# LcsNodes-Extension-Turnout-Servo-and-Rel.net
KiCad netlist of a schematic drawn in EasyEDA
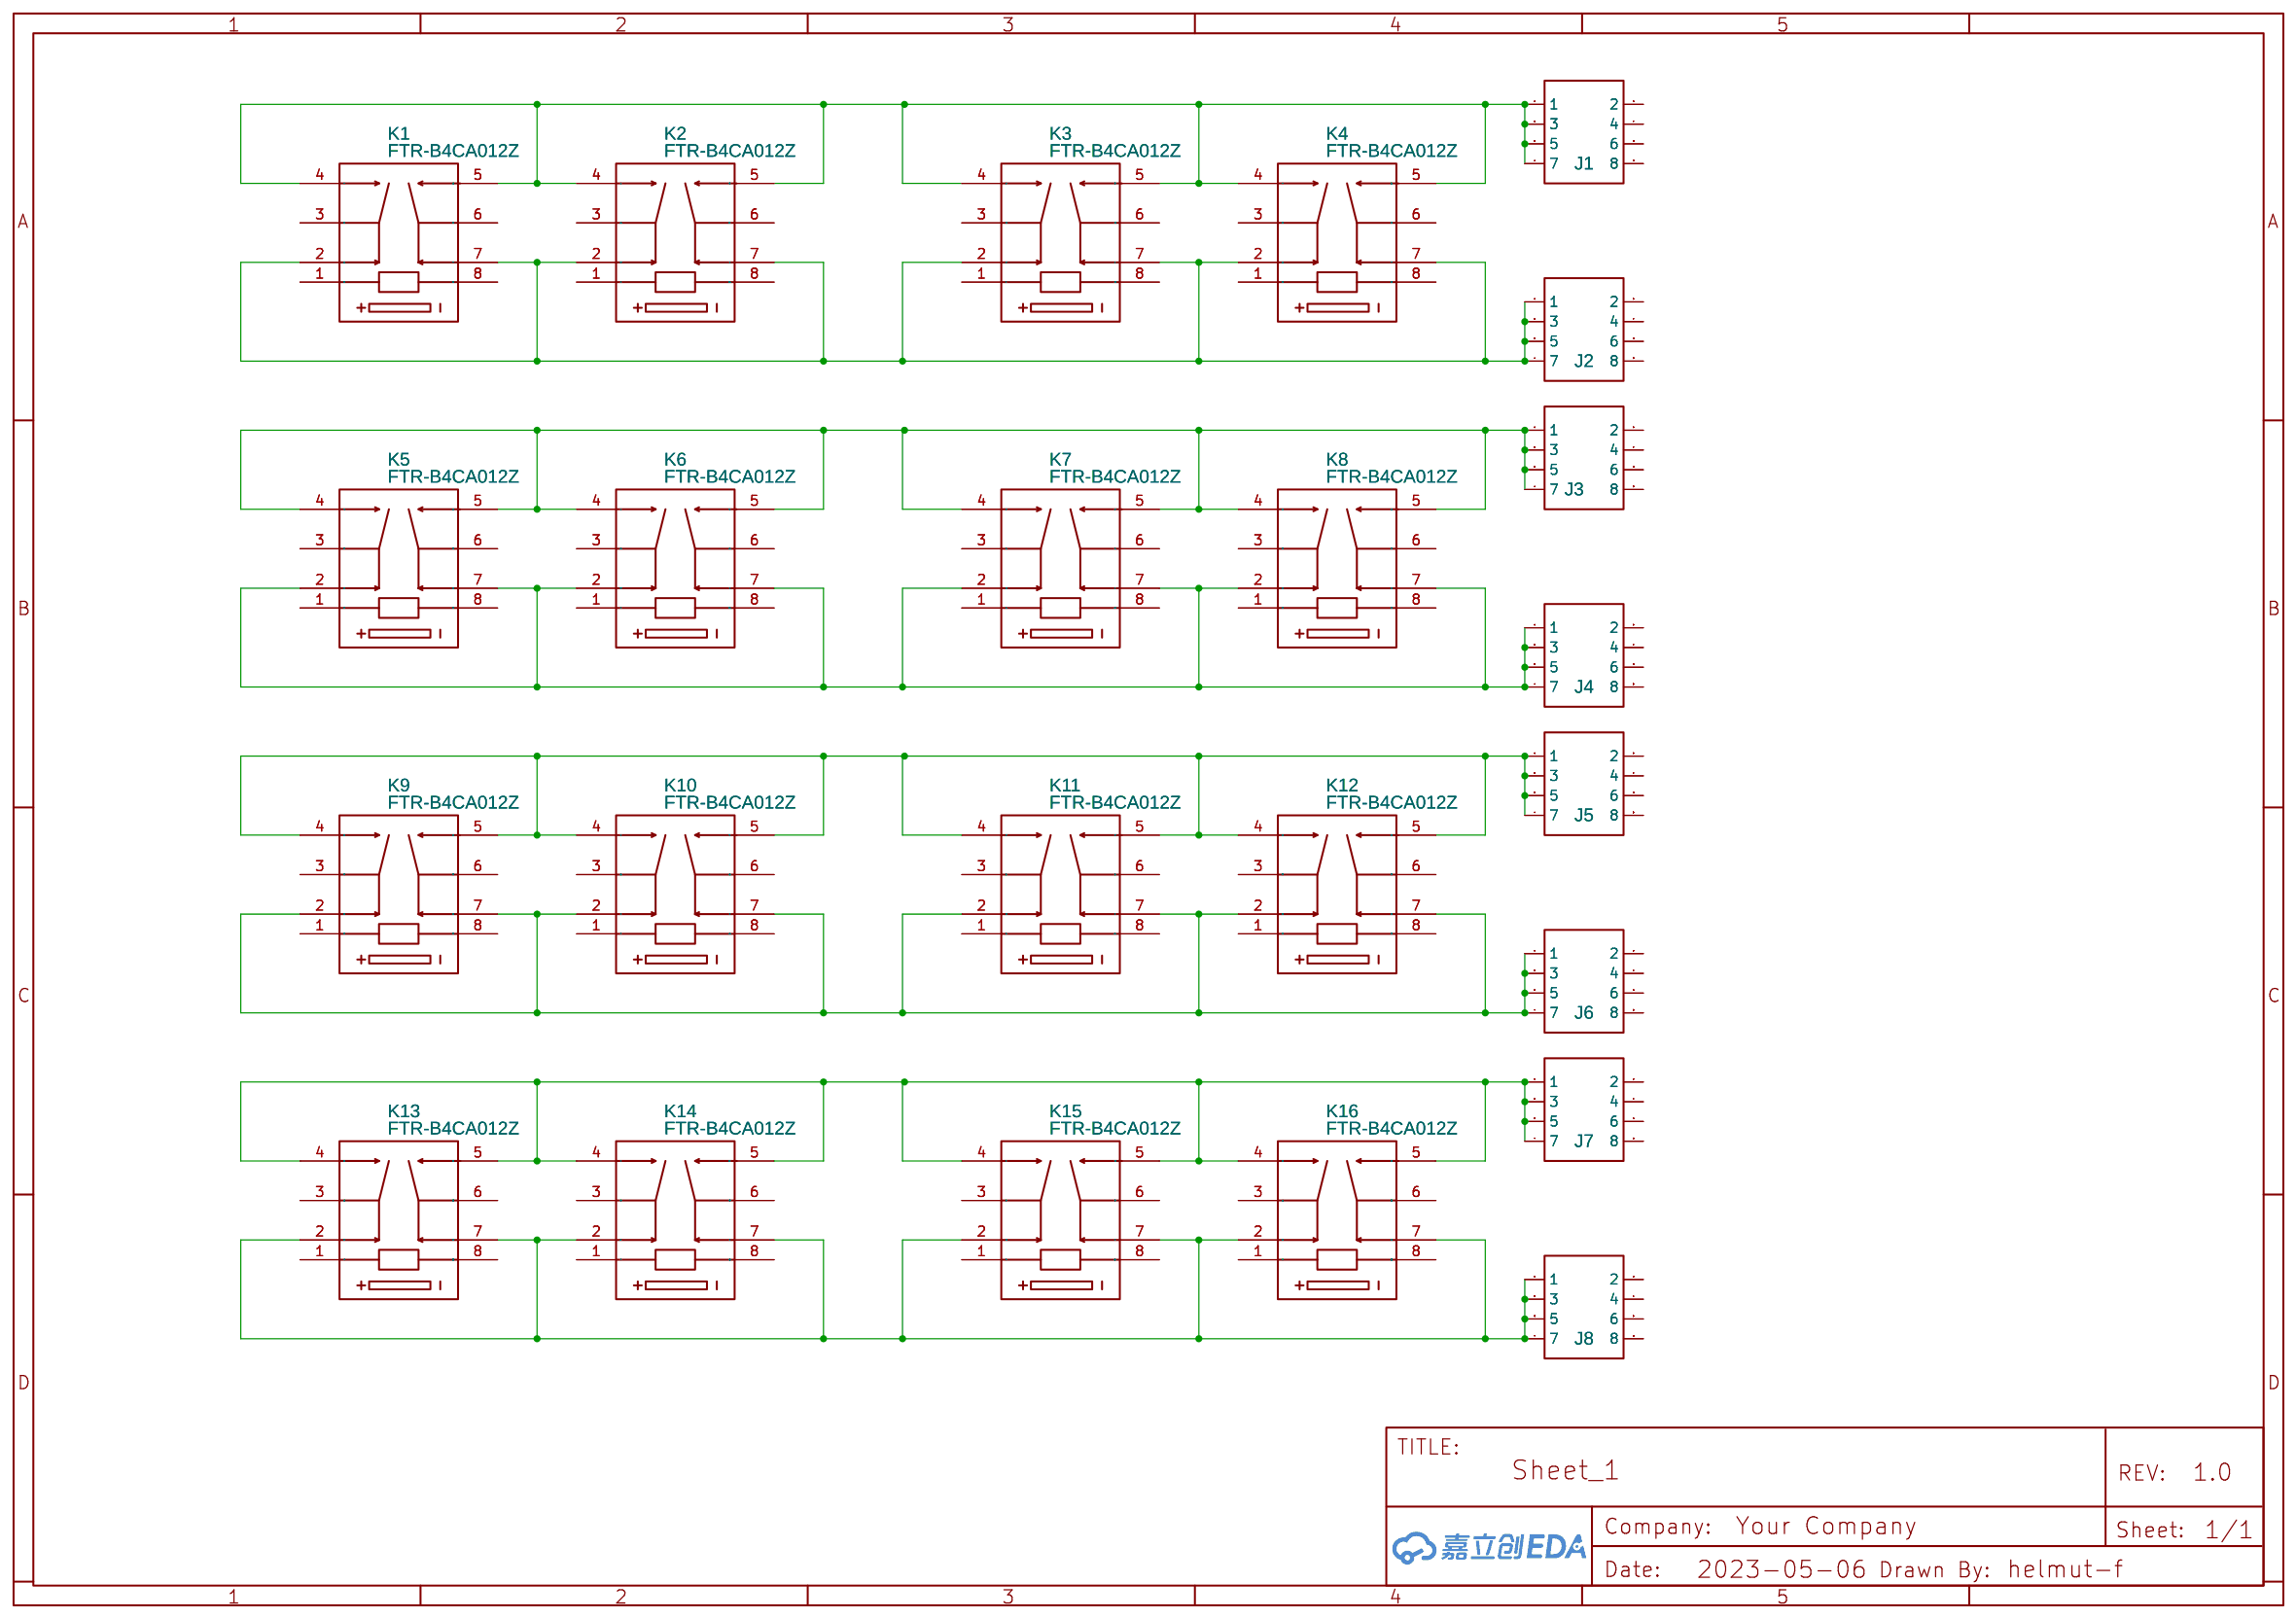
[diagram p0: Sheet_1]
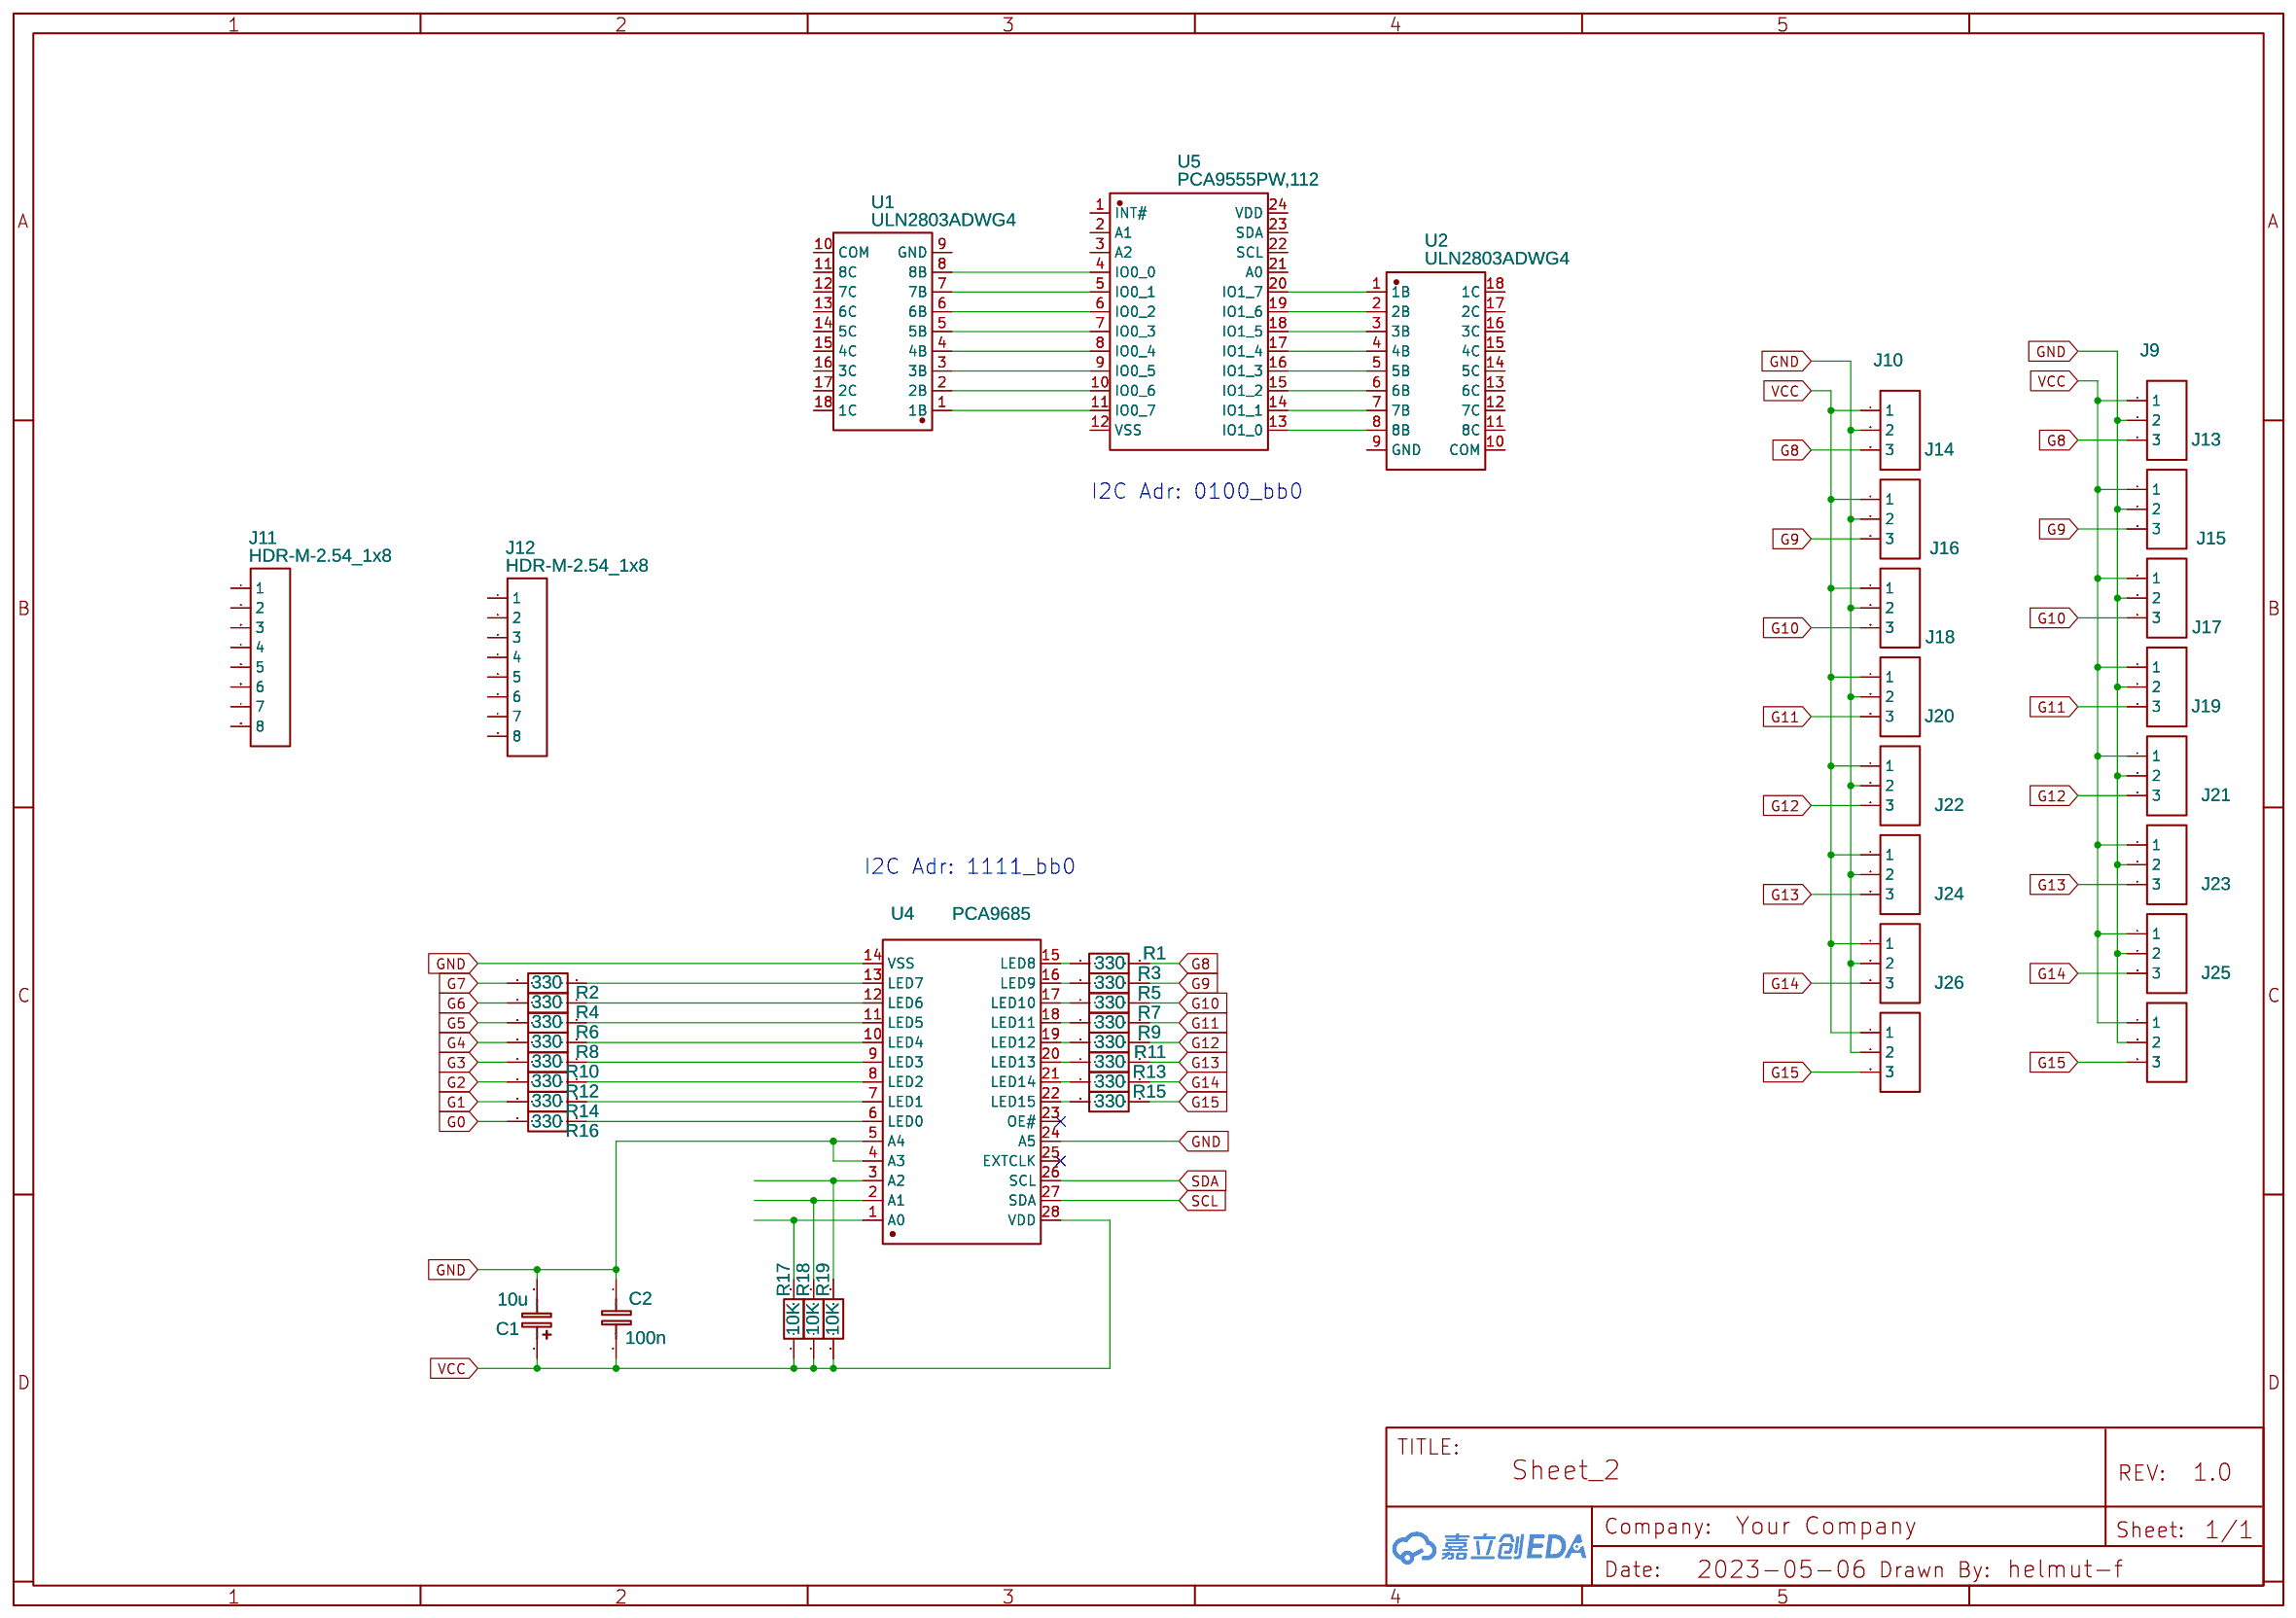
[diagram p1: Sheet_2]
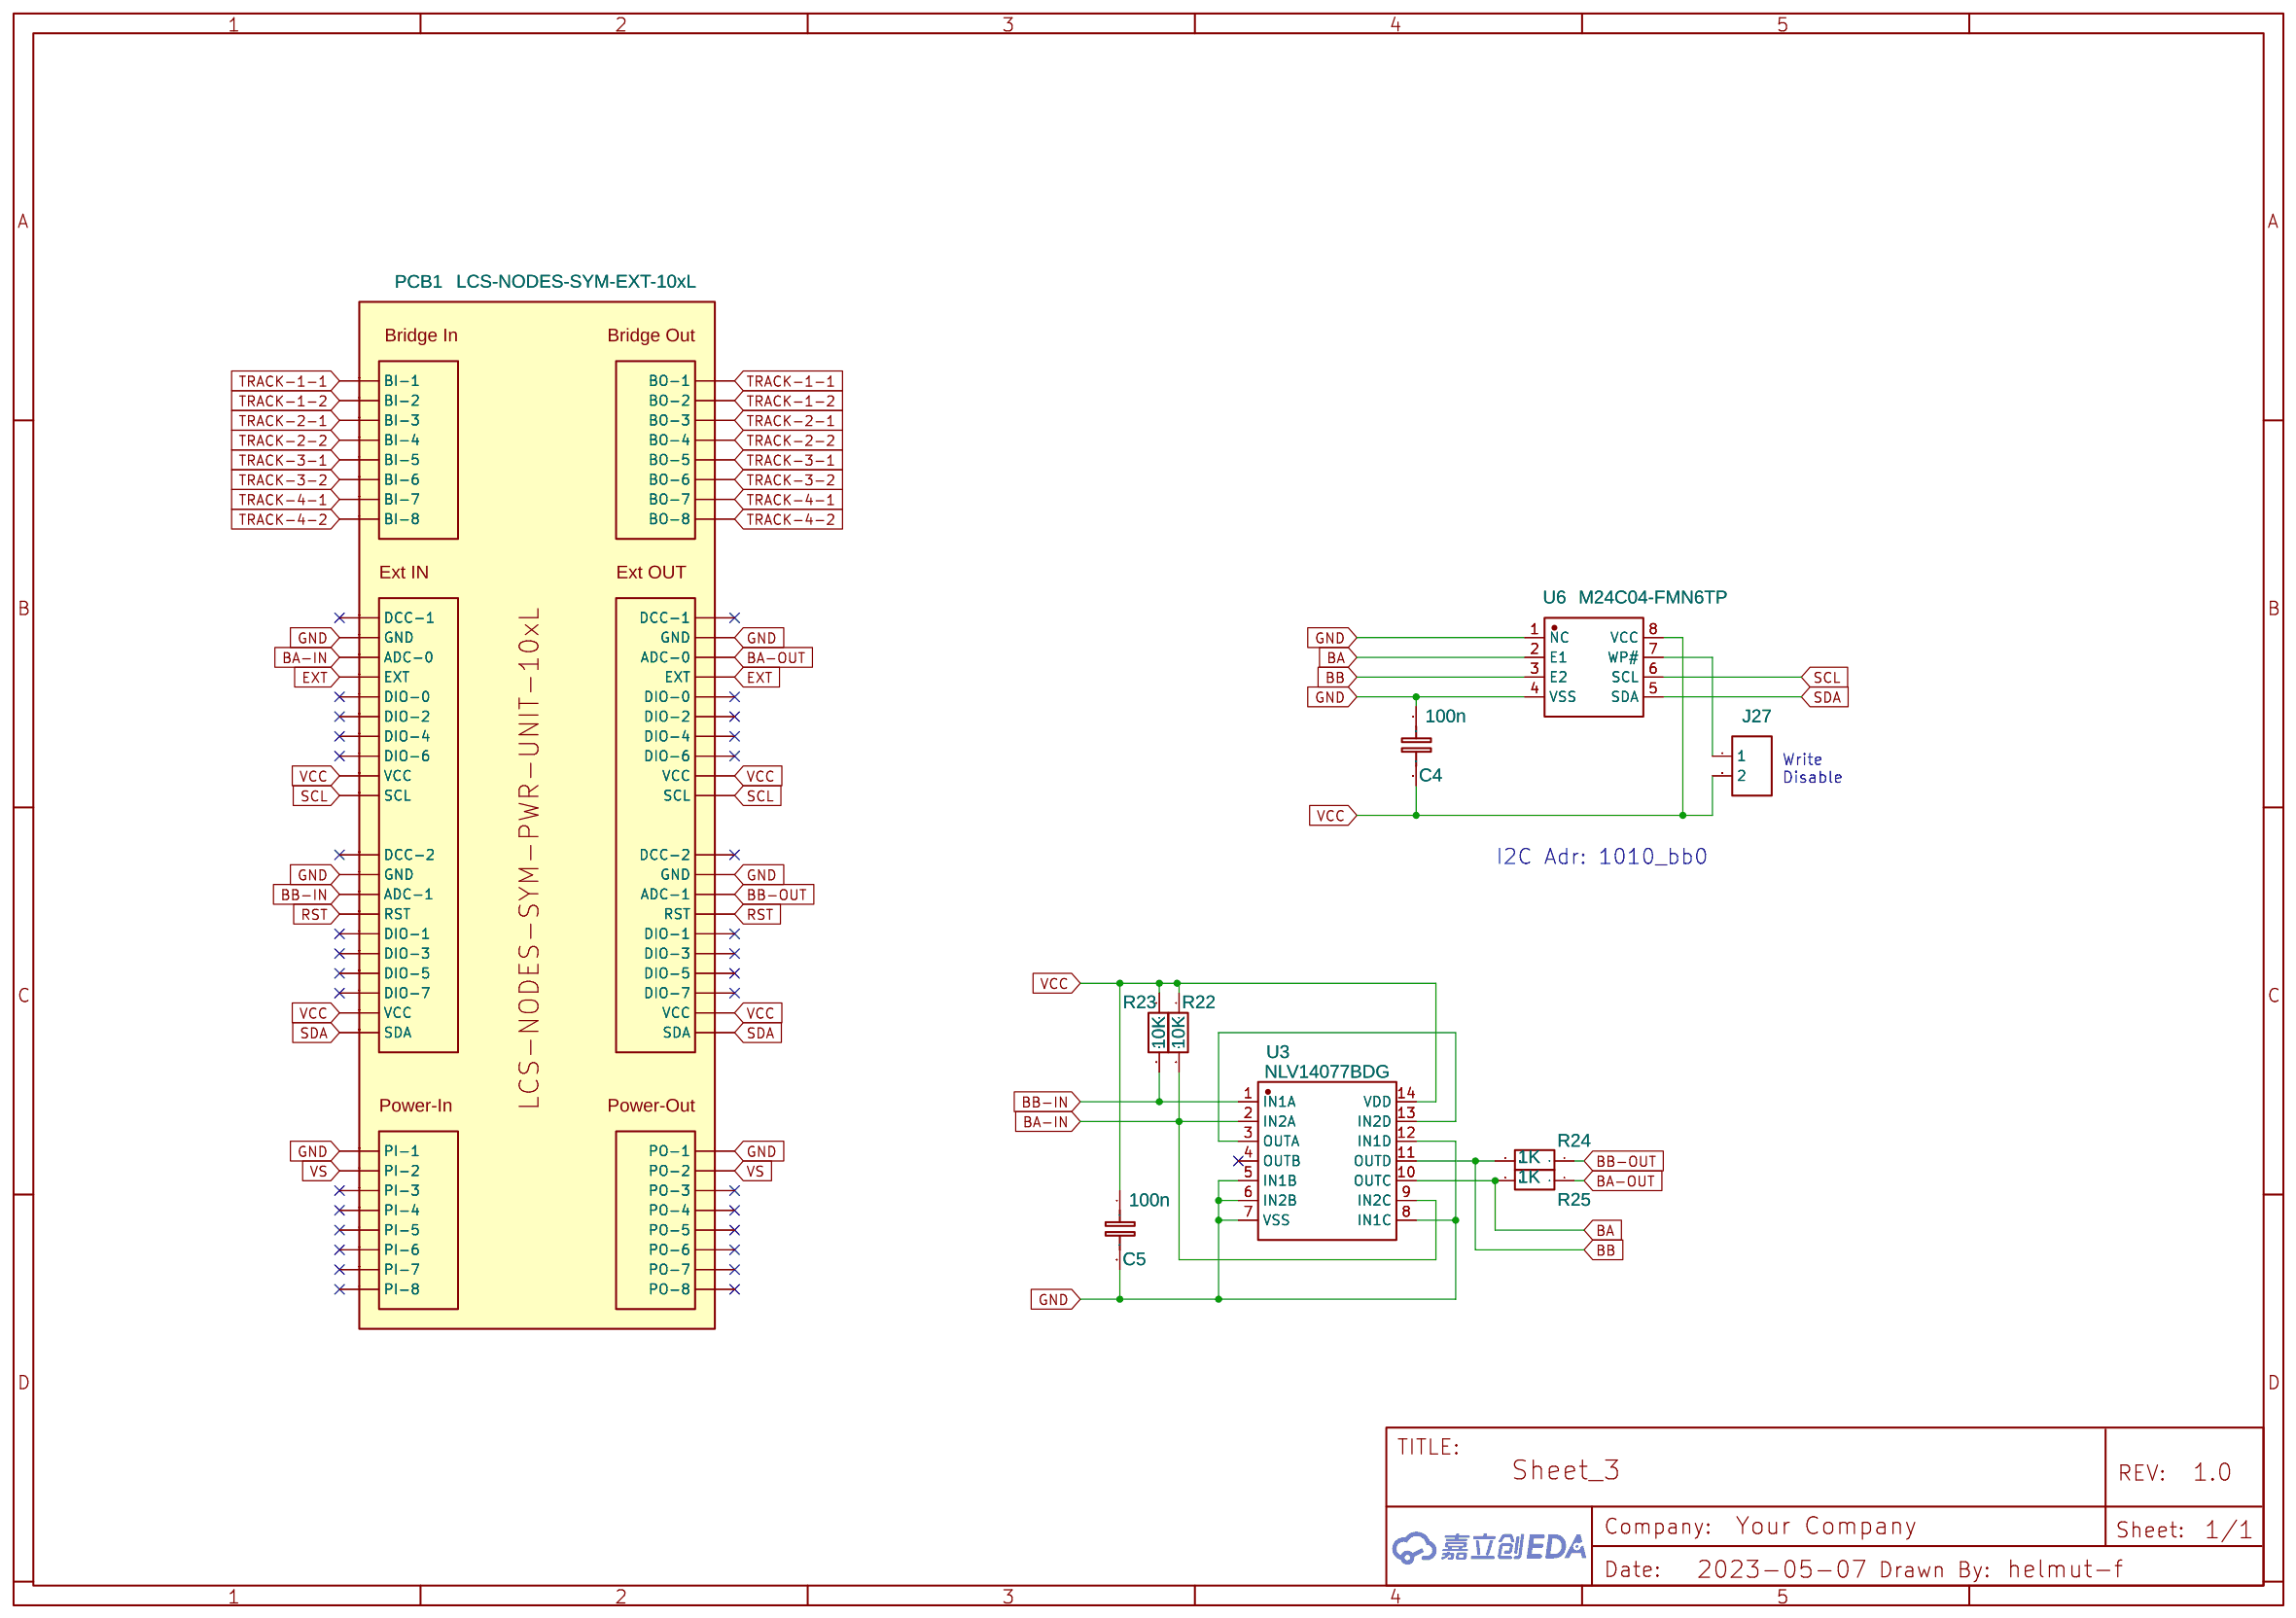
[diagram p2: Sheet_3]

(export (version "E")
  (design (tool "Eeschema 10.0.6"))
  (components
    (comp (ref "J1")
      (value "HDR-M-2.54_2x4")
      (fields (field (name "BOM_Supplier Part") "C58363"))
      (libsource (lib "") (part "HDR-M-2.54_2x4"))
    )
    (comp (ref "J2")
      (value "HDR-M-2.54_2x4")
      (fields (field (name "BOM_Supplier Part") "C58363"))
      (libsource (lib "") (part "HDR-M-2.54_2x4"))
    )
    (comp (ref "J3")
      (value "HDR-M-2.54_2x4")
      (fields (field (name "BOM_Supplier Part") "C58363"))
      (libsource (lib "") (part "HDR-M-2.54_2x4"))
    )
    (comp (ref "J4")
      (value "HDR-M-2.54_2x4")
      (fields (field (name "BOM_Supplier Part") "C58363"))
      (libsource (lib "") (part "HDR-M-2.54_2x4"))
    )
    (comp (ref "J5")
      (value "HDR-M-2.54_2x4")
      (fields (field (name "BOM_Supplier Part") "C58363"))
      (libsource (lib "") (part "HDR-M-2.54_2x4"))
    )
    (comp (ref "J6")
      (value "HDR-M-2.54_2x4")
      (fields (field (name "BOM_Supplier Part") "C58363"))
      (libsource (lib "") (part "HDR-M-2.54_2x4"))
    )
    (comp (ref "J7")
      (value "HDR-M-2.54_2x4")
      (fields (field (name "BOM_Supplier Part") "C58363"))
      (libsource (lib "") (part "HDR-M-2.54_2x4"))
    )
    (comp (ref "J8")
      (value "HDR-M-2.54_2x4")
      (fields (field (name "BOM_Supplier Part") "C58363"))
      (libsource (lib "") (part "HDR-M-2.54_2x4"))
    )
    (comp (ref "K1")
      (value "FTR-B4CA012Z")
      (fields (field (name "BOM_Supplier Part") "C1222347"))
      (libsource (lib "") (part "FTR-B4CA012Z"))
    )
    (comp (ref "K2")
      (value "FTR-B4CA012Z")
      (fields (field (name "BOM_Supplier Part") "C1222347"))
      (libsource (lib "") (part "FTR-B4CA012Z"))
    )
    (comp (ref "K3")
      (value "FTR-B4CA012Z")
      (fields (field (name "BOM_Supplier Part") "C1222347"))
      (libsource (lib "") (part "FTR-B4CA012Z"))
    )
    (comp (ref "K4")
      (value "FTR-B4CA012Z")
      (fields (field (name "BOM_Supplier Part") "C1222347"))
      (libsource (lib "") (part "FTR-B4CA012Z"))
    )
    (comp (ref "K5")
      (value "FTR-B4CA012Z")
      (fields (field (name "BOM_Supplier Part") "C1222347"))
      (libsource (lib "") (part "FTR-B4CA012Z"))
    )
    (comp (ref "K6")
      (value "FTR-B4CA012Z")
      (fields (field (name "BOM_Supplier Part") "C1222347"))
      (libsource (lib "") (part "FTR-B4CA012Z"))
    )
    (comp (ref "K7")
      (value "FTR-B4CA012Z")
      (fields (field (name "BOM_Supplier Part") "C1222347"))
      (libsource (lib "") (part "FTR-B4CA012Z"))
    )
    (comp (ref "K8")
      (value "FTR-B4CA012Z")
      (fields (field (name "BOM_Supplier Part") "C1222347"))
      (libsource (lib "") (part "FTR-B4CA012Z"))
    )
    (comp (ref "K9")
      (value "FTR-B4CA012Z")
      (fields (field (name "BOM_Supplier Part") "C1222347"))
      (libsource (lib "") (part "FTR-B4CA012Z"))
    )
    (comp (ref "K10")
      (value "FTR-B4CA012Z")
      (fields (field (name "BOM_Supplier Part") "C1222347"))
      (libsource (lib "") (part "FTR-B4CA012Z"))
    )
    (comp (ref "K11")
      (value "FTR-B4CA012Z")
      (fields (field (name "BOM_Supplier Part") "C1222347"))
      (libsource (lib "") (part "FTR-B4CA012Z"))
    )
    (comp (ref "K12")
      (value "FTR-B4CA012Z")
      (fields (field (name "BOM_Supplier Part") "C1222347"))
      (libsource (lib "") (part "FTR-B4CA012Z"))
    )
    (comp (ref "K13")
      (value "FTR-B4CA012Z")
      (fields (field (name "BOM_Supplier Part") "C1222347"))
      (libsource (lib "") (part "FTR-B4CA012Z"))
    )
    (comp (ref "K14")
      (value "FTR-B4CA012Z")
      (fields (field (name "BOM_Supplier Part") "C1222347"))
      (libsource (lib "") (part "FTR-B4CA012Z"))
    )
    (comp (ref "K15")
      (value "FTR-B4CA012Z")
      (fields (field (name "BOM_Supplier Part") "C1222347"))
      (libsource (lib "") (part "FTR-B4CA012Z"))
    )
    (comp (ref "K16")
      (value "FTR-B4CA012Z")
      (fields (field (name "BOM_Supplier Part") "C1222347"))
      (libsource (lib "") (part "FTR-B4CA012Z"))
    )
    (comp (ref "C1") (value "10u") (libsource (lib "") (part "CE_TH_D4.0×F1.5_EU")))
    (comp (ref "C2") (value "100n") (libsource (lib "") (part "C_0603_EU")))
    (comp (ref "J9")
      (value "HDR-M-2.54_1x3")
      (fields (field (name "BOM_Supplier Part") "C180248"))
      (libsource (lib "") (part "HDR-M-2.54_1x3"))
    )
    (comp (ref "J10")
      (value "HDR-M-2.54_1x3")
      (fields (field (name "BOM_Supplier Part") "C180248"))
      (libsource (lib "") (part "HDR-M-2.54_1x3"))
    )
    (comp (ref "J11")
      (value "HDR-M-2.54_1x8")
      (fields (field (name "BOM_Supplier Part") "C190820"))
      (libsource (lib "") (part "HDR-M-2.54_1x8"))
    )
    (comp (ref "J12")
      (value "HDR-M-2.54_1x8")
      (fields (field (name "BOM_Supplier Part") "C190820"))
      (libsource (lib "") (part "HDR-M-2.54_1x8"))
    )
    (comp (ref "J13")
      (value "HDR-M-2.54_1x3")
      (fields (field (name "BOM_Supplier Part") "C180248"))
      (libsource (lib "") (part "HDR-M-2.54_1x3"))
    )
    (comp (ref "J14")
      (value "HDR-M-2.54_1x3")
      (fields (field (name "BOM_Supplier Part") "C180248"))
      (libsource (lib "") (part "HDR-M-2.54_1x3"))
    )
    (comp (ref "J15")
      (value "HDR-M-2.54_1x3")
      (fields (field (name "BOM_Supplier Part") "C180248"))
      (libsource (lib "") (part "HDR-M-2.54_1x3"))
    )
    (comp (ref "J16")
      (value "HDR-M-2.54_1x3")
      (fields (field (name "BOM_Supplier Part") "C180248"))
      (libsource (lib "") (part "HDR-M-2.54_1x3"))
    )
    (comp (ref "J17")
      (value "HDR-M-2.54_1x3")
      (fields (field (name "BOM_Supplier Part") "C180248"))
      (libsource (lib "") (part "HDR-M-2.54_1x3"))
    )
    (comp (ref "J18")
      (value "HDR-M-2.54_1x3")
      (fields (field (name "BOM_Supplier Part") "C180248"))
      (libsource (lib "") (part "HDR-M-2.54_1x3"))
    )
    (comp (ref "J19")
      (value "HDR-M-2.54_1x3")
      (fields (field (name "BOM_Supplier Part") "C180248"))
      (libsource (lib "") (part "HDR-M-2.54_1x3"))
    )
    (comp (ref "J20")
      (value "HDR-M-2.54_1x3")
      (fields (field (name "BOM_Supplier Part") "C180248"))
      (libsource (lib "") (part "HDR-M-2.54_1x3"))
    )
    (comp (ref "J21")
      (value "HDR-M-2.54_1x3")
      (fields (field (name "BOM_Supplier Part") "C180248"))
      (libsource (lib "") (part "HDR-M-2.54_1x3"))
    )
    (comp (ref "J22")
      (value "HDR-M-2.54_1x3")
      (fields (field (name "BOM_Supplier Part") "C180248"))
      (libsource (lib "") (part "HDR-M-2.54_1x3"))
    )
    (comp (ref "J23")
      (value "HDR-M-2.54_1x3")
      (fields (field (name "BOM_Supplier Part") "C180248"))
      (libsource (lib "") (part "HDR-M-2.54_1x3"))
    )
    (comp (ref "J24")
      (value "HDR-M-2.54_1x3")
      (fields (field (name "BOM_Supplier Part") "C180248"))
      (libsource (lib "") (part "HDR-M-2.54_1x3"))
    )
    (comp (ref "J25")
      (value "HDR-M-2.54_1x3")
      (fields (field (name "BOM_Supplier Part") "C180248"))
      (libsource (lib "") (part "HDR-M-2.54_1x3"))
    )
    (comp (ref "J26")
      (value "HDR-M-2.54_1x3")
      (fields (field (name "BOM_Supplier Part") "C180248"))
      (libsource (lib "") (part "HDR-M-2.54_1x3"))
    )
    (comp (ref "R1") (value "330") (libsource (lib "") (part "R_AXIAL-0.3_EU")))
    (comp (ref "R2") (value "330") (libsource (lib "") (part "R_AXIAL-0.3_EU_1")))
    (comp (ref "R3") (value "330") (libsource (lib "") (part "R_AXIAL-0.3_EU")))
    (comp (ref "R4") (value "330") (libsource (lib "") (part "R_AXIAL-0.3_EU_1")))
    (comp (ref "R5") (value "330") (libsource (lib "") (part "R_AXIAL-0.3_EU")))
    (comp (ref "R6") (value "330") (libsource (lib "") (part "R_AXIAL-0.3_EU_1")))
    (comp (ref "R7") (value "330") (libsource (lib "") (part "R_AXIAL-0.3_EU")))
    (comp (ref "R8") (value "330") (libsource (lib "") (part "R_AXIAL-0.3_EU_1")))
    (comp (ref "R9") (value "330") (libsource (lib "") (part "R_AXIAL-0.3_EU")))
    (comp (ref "R10") (value "330") (libsource (lib "") (part "R_AXIAL-0.3_EU_1")))
    (comp (ref "R11") (value "330") (libsource (lib "") (part "R_AXIAL-0.3_EU")))
    (comp (ref "R12") (value "330") (libsource (lib "") (part "R_AXIAL-0.3_EU_1")))
    (comp (ref "R13") (value "330") (libsource (lib "") (part "R_AXIAL-0.3_EU")))
    (comp (ref "R14") (value "330") (libsource (lib "") (part "R_AXIAL-0.3_EU_1")))
    (comp (ref "R15") (value "330") (libsource (lib "") (part "R_AXIAL-0.3_EU")))
    (comp (ref "R16") (value "330") (libsource (lib "") (part "R_AXIAL-0.3_EU_1")))
    (comp (ref "R17") (value "10K") (libsource (lib "") (part "R_1206_EU")))
    (comp (ref "R18") (value "10K") (libsource (lib "") (part "R_1206_EU")))
    (comp (ref "R19") (value "10K") (libsource (lib "") (part "R_1206_EU")))
    (comp (ref "U1")
      (value "ULN2803ADWG4")
      (fields (field (name "BOM_Supplier Part") "C4365973"))
      (libsource (lib "") (part "ULN2803ADWG4"))
    )
    (comp (ref "U2")
      (value "ULN2803ADWG4")
      (fields (field (name "BOM_Supplier Part") "C4365973"))
      (libsource (lib "") (part "ULN2803ADWG4_1"))
    )
    (comp (ref "U4")
      (value "PCA9685")
      (fields
        (field (name "BOM_Manufacturer Part") "PCA9685PW/Q900,118")
        (field (name "BOM_Supplier Part") "C92206")
      )
      (libsource (lib "") (part "PCA9685PW/Q900,118"))
    )
    (comp (ref "U5")
      (value "PCA9555PW,112")
      (fields (field (name "BOM_Supplier Part") "C2688893"))
      (libsource (lib "") (part "PCA9555PW,112"))
    )
    (comp (ref "C4") (value "100n") (libsource (lib "") (part "C_0603_EU")))
    (comp (ref "C5") (value "100n") (libsource (lib "") (part "C_0603_EU")))
    (comp (ref "J27") (value "HDR-M-2.54_1x2") (libsource (lib "") (part "HDR-M-2.54_1x2")))
    (comp (ref "PCB1") (value "LCS-NODES-SYM-EXT-10xL") (libsource (lib "") (part "LCS-NODES-SYM-EXT-10xL")))
    (comp (ref "R22") (value "10K") (libsource (lib "") (part "R_AXIAL-0.3_EU_1")))
    (comp (ref "R23") (value "10K") (libsource (lib "") (part "R_AXIAL-0.3_EU_1")))
    (comp (ref "R24") (value "1K") (libsource (lib "") (part "R_AXIAL-0.3_EU")))
    (comp (ref "R25") (value "1K") (libsource (lib "") (part "R_AXIAL-0.3_EU")))
    (comp (ref "U3")
      (value "NLV14077BDG")
      (fields (field (name "Manufacturer") "onsemi(安森美)"))
      (libsource (lib "") (part "NLV14077BDG"))
    )
    (comp (ref "U6")
      (value "M24C04-FMN6TP")
      (fields (field (name "Manufacturer") "ST(意法半导体)"))
      (libsource (lib "") (part "M24C04-FMN6TP"))
    )
  )
  (nets
    (net (code "1") (name "BA") (class "Default")
      (node (ref "R25") (pin "2") (pinfunction "2_2") (pintype "unspecified"))
      (node (ref "U3") (pin "10") (pinfunction "OUTC_10") (pintype "unspecified"))
      (node (ref "U6") (pin "2") (pinfunction "E1_2") (pintype "unspecified"))
    )
    (net (code "2") (name "BA-IN") (class "Default")
      (node (ref "PCB1") (pin "22") (pinfunction "ADC-0_22") (pintype "unspecified"))
      (node (ref "R22") (pin "2") (pinfunction "2_2") (pintype "unspecified"))
      (node (ref "U3") (pin "2") (pinfunction "IN2A_2") (pintype "unspecified"))
      (node (ref "U3") (pin "9") (pinfunction "IN2C_9") (pintype "unspecified"))
    )
    (net (code "3") (name "BA-OUT") (class "Default")
      (node (ref "PCB1") (pin "62") (pinfunction "ADC-0_62") (pintype "unspecified"))
      (node (ref "R25") (pin "1") (pinfunction "1_1") (pintype "unspecified"))
    )
    (net (code "4") (name "BB") (class "Default")
      (node (ref "R24") (pin "2") (pinfunction "2_2") (pintype "unspecified"))
      (node (ref "U3") (pin "11") (pinfunction "OUTD_11") (pintype "unspecified"))
      (node (ref "U6") (pin "3") (pinfunction "E2_3") (pintype "unspecified"))
    )
    (net (code "5") (name "BB-IN") (class "Default")
      (node (ref "PCB1") (pin "32") (pinfunction "ADC-1_32") (pintype "unspecified"))
      (node (ref "R23") (pin "2") (pinfunction "2_2") (pintype "unspecified"))
      (node (ref "U3") (pin "1") (pinfunction "IN1A_1") (pintype "unspecified"))
    )
    (net (code "6") (name "BB-OUT") (class "Default")
      (node (ref "PCB1") (pin "72") (pinfunction "ADC-1_72") (pintype "unspecified"))
      (node (ref "R24") (pin "1") (pinfunction "1_1") (pintype "unspecified"))
    )
    (net (code "7") (name "EXT") (class "Default")
      (node (ref "PCB1") (pin "23") (pinfunction "EXT_23") (pintype "unspecified"))
      (node (ref "PCB1") (pin "63") (pinfunction "EXT_63") (pintype "unspecified"))
    )
    (net (code "8") (name "G0") (class "Default")
      (node (ref "R16") (pin "2") (pinfunction "2_2") (pintype "unspecified"))
    )
    (net (code "9") (name "G1") (class "Default")
      (node (ref "R14") (pin "2") (pinfunction "2_2") (pintype "unspecified"))
    )
    (net (code "10") (name "G2") (class "Default")
      (node (ref "R12") (pin "2") (pinfunction "2_2") (pintype "unspecified"))
    )
    (net (code "11") (name "G3") (class "Default")
      (node (ref "R10") (pin "2") (pinfunction "2_2") (pintype "unspecified"))
    )
    (net (code "12") (name "G4") (class "Default")
      (node (ref "R8") (pin "2") (pinfunction "2_2") (pintype "unspecified"))
    )
    (net (code "13") (name "G5") (class "Default")
      (node (ref "R6") (pin "2") (pinfunction "2_2") (pintype "unspecified"))
    )
    (net (code "14") (name "G6") (class "Default")
      (node (ref "R4") (pin "2") (pinfunction "2_2") (pintype "unspecified"))
    )
    (net (code "15") (name "G7") (class "Default")
      (node (ref "R2") (pin "2") (pinfunction "2_2") (pintype "unspecified"))
    )
    (net (code "16") (name "G8") (class "Default")
      (node (ref "J10") (pin "3") (pinfunction "3_3") (pintype "input"))
      (node (ref "J9") (pin "3") (pinfunction "3_3") (pintype "input"))
      (node (ref "R1") (pin "2") (pinfunction "2_2") (pintype "unspecified"))
    )
    (net (code "17") (name "G9") (class "Default")
      (node (ref "J13") (pin "3") (pinfunction "3_3") (pintype "input"))
      (node (ref "J14") (pin "3") (pinfunction "3_3") (pintype "input"))
      (node (ref "R3") (pin "2") (pinfunction "2_2") (pintype "unspecified"))
    )
    (net (code "18") (name "G10") (class "Default")
      (node (ref "J15") (pin "3") (pinfunction "3_3") (pintype "input"))
      (node (ref "J16") (pin "3") (pinfunction "3_3") (pintype "input"))
      (node (ref "R5") (pin "2") (pinfunction "2_2") (pintype "unspecified"))
    )
    (net (code "19") (name "G11") (class "Default")
      (node (ref "J17") (pin "3") (pinfunction "3_3") (pintype "input"))
      (node (ref "J18") (pin "3") (pinfunction "3_3") (pintype "input"))
      (node (ref "R7") (pin "2") (pinfunction "2_2") (pintype "unspecified"))
    )
    (net (code "20") (name "G12") (class "Default")
      (node (ref "J19") (pin "3") (pinfunction "3_3") (pintype "input"))
      (node (ref "J20") (pin "3") (pinfunction "3_3") (pintype "input"))
      (node (ref "R9") (pin "2") (pinfunction "2_2") (pintype "unspecified"))
    )
    (net (code "21") (name "G13") (class "Default")
      (node (ref "J21") (pin "3") (pinfunction "3_3") (pintype "input"))
      (node (ref "J22") (pin "3") (pinfunction "3_3") (pintype "input"))
      (node (ref "R11") (pin "2") (pinfunction "2_2") (pintype "unspecified"))
    )
    (net (code "22") (name "G14") (class "Default")
      (node (ref "J23") (pin "3") (pinfunction "3_3") (pintype "input"))
      (node (ref "J24") (pin "3") (pinfunction "3_3") (pintype "input"))
      (node (ref "R13") (pin "2") (pinfunction "2_2") (pintype "unspecified"))
    )
    (net (code "23") (name "G15") (class "Default")
      (node (ref "J25") (pin "3") (pinfunction "3_3") (pintype "input"))
      (node (ref "J26") (pin "3") (pinfunction "3_3") (pintype "input"))
      (node (ref "R15") (pin "2") (pinfunction "2_2") (pintype "unspecified"))
    )
    (net (code "24") (name "GND") (class "Default")
      (node (ref "C1") (pin "2") (pinfunction "2_2") (pintype "unspecified"))
      (node (ref "C2") (pin "1") (pinfunction "1_1") (pintype "unspecified"))
      (node (ref "C4") (pin "1") (pinfunction "1_1") (pintype "unspecified"))
      (node (ref "C5") (pin "2") (pinfunction "2_2") (pintype "unspecified"))
      (node (ref "J10") (pin "2") (pinfunction "2_2") (pintype "input"))
      (node (ref "J13") (pin "2") (pinfunction "2_2") (pintype "input"))
      (node (ref "J14") (pin "2") (pinfunction "2_2") (pintype "input"))
      (node (ref "J15") (pin "2") (pinfunction "2_2") (pintype "input"))
      (node (ref "J16") (pin "2") (pinfunction "2_2") (pintype "input"))
      (node (ref "J17") (pin "2") (pinfunction "2_2") (pintype "input"))
      (node (ref "J18") (pin "2") (pinfunction "2_2") (pintype "input"))
      (node (ref "J19") (pin "2") (pinfunction "2_2") (pintype "input"))
      (node (ref "J20") (pin "2") (pinfunction "2_2") (pintype "input"))
      (node (ref "J21") (pin "2") (pinfunction "2_2") (pintype "input"))
      (node (ref "J22") (pin "2") (pinfunction "2_2") (pintype "input"))
      (node (ref "J23") (pin "2") (pinfunction "2_2") (pintype "input"))
      (node (ref "J24") (pin "2") (pinfunction "2_2") (pintype "input"))
      (node (ref "J25") (pin "2") (pinfunction "2_2") (pintype "input"))
      (node (ref "J26") (pin "2") (pinfunction "2_2") (pintype "input"))
      (node (ref "J9") (pin "2") (pinfunction "2_2") (pintype "input"))
      (node (ref "PCB1") (pin "21") (pinfunction "GND_21") (pintype "unspecified"))
      (node (ref "PCB1") (pin "31") (pinfunction "GND_31") (pintype "unspecified"))
      (node (ref "PCB1") (pin "40") (pinfunction "PI-1_40") (pintype "unspecified"))
      (node (ref "PCB1") (pin "61") (pinfunction "GND_61") (pintype "unspecified"))
      (node (ref "PCB1") (pin "71") (pinfunction "GND_71") (pintype "unspecified"))
      (node (ref "PCB1") (pin "80") (pinfunction "PO-1_80") (pintype "unspecified"))
      (node (ref "U3") (pin "12") (pinfunction "IN1D_12") (pintype "unspecified"))
      (node (ref "U3") (pin "5") (pinfunction "IN1B_5") (pintype "unspecified"))
      (node (ref "U3") (pin "6") (pinfunction "IN2B_6") (pintype "unspecified"))
      (node (ref "U3") (pin "7") (pinfunction "VSS_7") (pintype "unspecified"))
      (node (ref "U3") (pin "8") (pinfunction "IN1C_8") (pintype "unspecified"))
      (node (ref "U4") (pin "14") (pinfunction "VSS_14") (pintype "unspecified"))
      (node (ref "U4") (pin "24") (pinfunction "A5_24") (pintype "unspecified"))
      (node (ref "U4") (pin "4") (pinfunction "A3_4") (pintype "unspecified"))
      (node (ref "U4") (pin "5") (pinfunction "A4_5") (pintype "unspecified"))
      (node (ref "U6") (pin "1") (pinfunction "NC_1") (pintype "unspecified"))
      (node (ref "U6") (pin "4") (pinfunction "VSS_4") (pintype "unspecified"))
    )
    (net (code "25") (name "Net-(J1-Pad1)") (class "Default")
      (node (ref "J1") (pin "1") (pinfunction "1_1") (pintype "unspecified"))
      (node (ref "J1") (pin "3") (pinfunction "3_3") (pintype "unspecified"))
      (node (ref "J1") (pin "5") (pinfunction "5_5") (pintype "unspecified"))
      (node (ref "J1") (pin "7") (pinfunction "7_7") (pintype "unspecified"))
      (node (ref "K1") (pin "4") (pinfunction "4_4") (pintype "unspecified"))
      (node (ref "K1") (pin "5") (pinfunction "5_5") (pintype "unspecified"))
      (node (ref "K2") (pin "4") (pinfunction "4_4") (pintype "unspecified"))
      (node (ref "K2") (pin "5") (pinfunction "5_5") (pintype "unspecified"))
      (node (ref "K3") (pin "4") (pinfunction "4_4") (pintype "unspecified"))
      (node (ref "K3") (pin "5") (pinfunction "5_5") (pintype "unspecified"))
      (node (ref "K4") (pin "4") (pinfunction "4_4") (pintype "unspecified"))
      (node (ref "K4") (pin "5") (pinfunction "5_5") (pintype "unspecified"))
    )
    (net (code "26") (name "Net-(J2-Pad1)") (class "Default")
      (node (ref "J2") (pin "1") (pinfunction "1_1") (pintype "unspecified"))
      (node (ref "J2") (pin "3") (pinfunction "3_3") (pintype "unspecified"))
      (node (ref "J2") (pin "5") (pinfunction "5_5") (pintype "unspecified"))
      (node (ref "J2") (pin "7") (pinfunction "7_7") (pintype "unspecified"))
      (node (ref "K1") (pin "2") (pinfunction "2_2") (pintype "unspecified"))
      (node (ref "K1") (pin "7") (pinfunction "7_7") (pintype "unspecified"))
      (node (ref "K2") (pin "2") (pinfunction "2_2") (pintype "unspecified"))
      (node (ref "K2") (pin "7") (pinfunction "7_7") (pintype "unspecified"))
      (node (ref "K3") (pin "2") (pinfunction "2_2") (pintype "unspecified"))
      (node (ref "K3") (pin "7") (pinfunction "7_7") (pintype "unspecified"))
      (node (ref "K4") (pin "2") (pinfunction "2_2") (pintype "unspecified"))
      (node (ref "K4") (pin "7") (pinfunction "7_7") (pintype "unspecified"))
    )
    (net (code "27") (name "Net-(J3-Pad1)") (class "Default")
      (node (ref "J3") (pin "1") (pinfunction "1_1") (pintype "unspecified"))
      (node (ref "J3") (pin "3") (pinfunction "3_3") (pintype "unspecified"))
      (node (ref "J3") (pin "5") (pinfunction "5_5") (pintype "unspecified"))
      (node (ref "J3") (pin "7") (pinfunction "7_7") (pintype "unspecified"))
      (node (ref "K5") (pin "4") (pinfunction "4_4") (pintype "unspecified"))
      (node (ref "K5") (pin "5") (pinfunction "5_5") (pintype "unspecified"))
      (node (ref "K6") (pin "4") (pinfunction "4_4") (pintype "unspecified"))
      (node (ref "K6") (pin "5") (pinfunction "5_5") (pintype "unspecified"))
      (node (ref "K7") (pin "4") (pinfunction "4_4") (pintype "unspecified"))
      (node (ref "K7") (pin "5") (pinfunction "5_5") (pintype "unspecified"))
      (node (ref "K8") (pin "4") (pinfunction "4_4") (pintype "unspecified"))
      (node (ref "K8") (pin "5") (pinfunction "5_5") (pintype "unspecified"))
    )
    (net (code "28") (name "Net-(J4-Pad1)") (class "Default")
      (node (ref "J4") (pin "1") (pinfunction "1_1") (pintype "unspecified"))
      (node (ref "J4") (pin "3") (pinfunction "3_3") (pintype "unspecified"))
      (node (ref "J4") (pin "5") (pinfunction "5_5") (pintype "unspecified"))
      (node (ref "J4") (pin "7") (pinfunction "7_7") (pintype "unspecified"))
      (node (ref "K5") (pin "2") (pinfunction "2_2") (pintype "unspecified"))
      (node (ref "K5") (pin "7") (pinfunction "7_7") (pintype "unspecified"))
      (node (ref "K6") (pin "2") (pinfunction "2_2") (pintype "unspecified"))
      (node (ref "K6") (pin "7") (pinfunction "7_7") (pintype "unspecified"))
      (node (ref "K7") (pin "2") (pinfunction "2_2") (pintype "unspecified"))
      (node (ref "K7") (pin "7") (pinfunction "7_7") (pintype "unspecified"))
      (node (ref "K8") (pin "2") (pinfunction "2_2") (pintype "unspecified"))
      (node (ref "K8") (pin "7") (pinfunction "7_7") (pintype "unspecified"))
    )
    (net (code "29") (name "Net-(J5-Pad1)") (class "Default")
      (node (ref "J5") (pin "1") (pinfunction "1_1") (pintype "unspecified"))
      (node (ref "J5") (pin "3") (pinfunction "3_3") (pintype "unspecified"))
      (node (ref "J5") (pin "5") (pinfunction "5_5") (pintype "unspecified"))
      (node (ref "J5") (pin "7") (pinfunction "7_7") (pintype "unspecified"))
      (node (ref "K10") (pin "4") (pinfunction "4_4") (pintype "unspecified"))
      (node (ref "K10") (pin "5") (pinfunction "5_5") (pintype "unspecified"))
      (node (ref "K11") (pin "4") (pinfunction "4_4") (pintype "unspecified"))
      (node (ref "K11") (pin "5") (pinfunction "5_5") (pintype "unspecified"))
      (node (ref "K12") (pin "4") (pinfunction "4_4") (pintype "unspecified"))
      (node (ref "K12") (pin "5") (pinfunction "5_5") (pintype "unspecified"))
      (node (ref "K9") (pin "4") (pinfunction "4_4") (pintype "unspecified"))
      (node (ref "K9") (pin "5") (pinfunction "5_5") (pintype "unspecified"))
    )
    (net (code "30") (name "Net-(J6-Pad1)") (class "Default")
      (node (ref "J6") (pin "1") (pinfunction "1_1") (pintype "unspecified"))
      (node (ref "J6") (pin "3") (pinfunction "3_3") (pintype "unspecified"))
      (node (ref "J6") (pin "5") (pinfunction "5_5") (pintype "unspecified"))
      (node (ref "J6") (pin "7") (pinfunction "7_7") (pintype "unspecified"))
      (node (ref "K10") (pin "2") (pinfunction "2_2") (pintype "unspecified"))
      (node (ref "K10") (pin "7") (pinfunction "7_7") (pintype "unspecified"))
      (node (ref "K11") (pin "2") (pinfunction "2_2") (pintype "unspecified"))
      (node (ref "K11") (pin "7") (pinfunction "7_7") (pintype "unspecified"))
      (node (ref "K12") (pin "2") (pinfunction "2_2") (pintype "unspecified"))
      (node (ref "K12") (pin "7") (pinfunction "7_7") (pintype "unspecified"))
      (node (ref "K9") (pin "2") (pinfunction "2_2") (pintype "unspecified"))
      (node (ref "K9") (pin "7") (pinfunction "7_7") (pintype "unspecified"))
    )
    (net (code "31") (name "Net-(J7-Pad1)") (class "Default")
      (node (ref "J7") (pin "1") (pinfunction "1_1") (pintype "unspecified"))
      (node (ref "J7") (pin "3") (pinfunction "3_3") (pintype "unspecified"))
      (node (ref "J7") (pin "5") (pinfunction "5_5") (pintype "unspecified"))
      (node (ref "J7") (pin "7") (pinfunction "7_7") (pintype "unspecified"))
      (node (ref "K13") (pin "4") (pinfunction "4_4") (pintype "unspecified"))
      (node (ref "K13") (pin "5") (pinfunction "5_5") (pintype "unspecified"))
      (node (ref "K14") (pin "4") (pinfunction "4_4") (pintype "unspecified"))
      (node (ref "K14") (pin "5") (pinfunction "5_5") (pintype "unspecified"))
      (node (ref "K15") (pin "4") (pinfunction "4_4") (pintype "unspecified"))
      (node (ref "K15") (pin "5") (pinfunction "5_5") (pintype "unspecified"))
      (node (ref "K16") (pin "4") (pinfunction "4_4") (pintype "unspecified"))
      (node (ref "K16") (pin "5") (pinfunction "5_5") (pintype "unspecified"))
    )
    (net (code "32") (name "Net-(J8-Pad1)") (class "Default")
      (node (ref "J8") (pin "1") (pinfunction "1_1") (pintype "unspecified"))
      (node (ref "J8") (pin "3") (pinfunction "3_3") (pintype "unspecified"))
      (node (ref "J8") (pin "5") (pinfunction "5_5") (pintype "unspecified"))
      (node (ref "J8") (pin "7") (pinfunction "7_7") (pintype "unspecified"))
      (node (ref "K13") (pin "2") (pinfunction "2_2") (pintype "unspecified"))
      (node (ref "K13") (pin "7") (pinfunction "7_7") (pintype "unspecified"))
      (node (ref "K14") (pin "2") (pinfunction "2_2") (pintype "unspecified"))
      (node (ref "K14") (pin "7") (pinfunction "7_7") (pintype "unspecified"))
      (node (ref "K15") (pin "2") (pinfunction "2_2") (pintype "unspecified"))
      (node (ref "K15") (pin "7") (pinfunction "7_7") (pintype "unspecified"))
      (node (ref "K16") (pin "2") (pinfunction "2_2") (pintype "unspecified"))
      (node (ref "K16") (pin "7") (pinfunction "7_7") (pintype "unspecified"))
    )
    (net (code "33") (name "Net-(U1-1B)") (class "Default")
      (node (ref "U1") (pin "1") (pinfunction "1B_1") (pintype "unspecified"))
      (node (ref "U5") (pin "11") (pinfunction "IO0_7_11") (pintype "unspecified"))
    )
    (net (code "34") (name "Net-(U1-2B)") (class "Default")
      (node (ref "U1") (pin "2") (pinfunction "2B_2") (pintype "unspecified"))
      (node (ref "U5") (pin "10") (pinfunction "IO0_6_10") (pintype "unspecified"))
    )
    (net (code "35") (name "Net-(U1-3B)") (class "Default")
      (node (ref "U1") (pin "3") (pinfunction "3B_3") (pintype "unspecified"))
      (node (ref "U5") (pin "9") (pinfunction "IO0_5_9") (pintype "unspecified"))
    )
    (net (code "36") (name "Net-(U1-4B)") (class "Default")
      (node (ref "U1") (pin "4") (pinfunction "4B_4") (pintype "unspecified"))
      (node (ref "U5") (pin "8") (pinfunction "IO0_4_8") (pintype "unspecified"))
    )
    (net (code "37") (name "Net-(U1-5B)") (class "Default")
      (node (ref "U1") (pin "5") (pinfunction "5B_5") (pintype "unspecified"))
      (node (ref "U5") (pin "7") (pinfunction "IO0_3_7") (pintype "unspecified"))
    )
    (net (code "38") (name "Net-(U1-6B)") (class "Default")
      (node (ref "U1") (pin "6") (pinfunction "6B_6") (pintype "unspecified"))
      (node (ref "U5") (pin "6") (pinfunction "IO0_2_6") (pintype "unspecified"))
    )
    (net (code "39") (name "Net-(U1-7B)") (class "Default")
      (node (ref "U1") (pin "7") (pinfunction "7B_7") (pintype "unspecified"))
      (node (ref "U5") (pin "5") (pinfunction "IO0_1_5") (pintype "unspecified"))
    )
    (net (code "40") (name "Net-(U1-8B)") (class "Default")
      (node (ref "U1") (pin "8") (pinfunction "8B_8") (pintype "unspecified"))
      (node (ref "U5") (pin "4") (pinfunction "IO0_0_4") (pintype "unspecified"))
    )
    (net (code "41") (name "Net-(U2-1B)") (class "Default")
      (node (ref "U2") (pin "1") (pinfunction "1B_1") (pintype "unspecified"))
      (node (ref "U5") (pin "20") (pinfunction "IO1_7_20") (pintype "unspecified"))
    )
    (net (code "42") (name "Net-(U2-2B)") (class "Default")
      (node (ref "U2") (pin "2") (pinfunction "2B_2") (pintype "unspecified"))
      (node (ref "U5") (pin "19") (pinfunction "IO1_6_19") (pintype "unspecified"))
    )
    (net (code "43") (name "Net-(U2-3B)") (class "Default")
      (node (ref "U2") (pin "3") (pinfunction "3B_3") (pintype "unspecified"))
      (node (ref "U5") (pin "18") (pinfunction "IO1_5_18") (pintype "unspecified"))
    )
    (net (code "44") (name "Net-(U2-4B)") (class "Default")
      (node (ref "U2") (pin "4") (pinfunction "4B_4") (pintype "unspecified"))
      (node (ref "U5") (pin "17") (pinfunction "IO1_4_17") (pintype "unspecified"))
    )
    (net (code "45") (name "Net-(U2-5B)") (class "Default")
      (node (ref "U2") (pin "5") (pinfunction "5B_5") (pintype "unspecified"))
      (node (ref "U5") (pin "16") (pinfunction "IO1_3_16") (pintype "unspecified"))
    )
    (net (code "46") (name "Net-(U2-6B)") (class "Default")
      (node (ref "U2") (pin "6") (pinfunction "6B_6") (pintype "unspecified"))
      (node (ref "U5") (pin "15") (pinfunction "IO1_2_15") (pintype "unspecified"))
    )
    (net (code "47") (name "Net-(U2-7B)") (class "Default")
      (node (ref "U2") (pin "7") (pinfunction "7B_7") (pintype "unspecified"))
      (node (ref "U5") (pin "14") (pinfunction "IO1_1_14") (pintype "unspecified"))
    )
    (net (code "48") (name "Net-(U2-8B)") (class "Default")
      (node (ref "U2") (pin "8") (pinfunction "8B_8") (pintype "unspecified"))
      (node (ref "U5") (pin "13") (pinfunction "IO1_0_13") (pintype "unspecified"))
    )
    (net (code "49") (name "Net-(U3-IN2D)") (class "Default")
      (node (ref "U3") (pin "13") (pinfunction "IN2D_13") (pintype "unspecified"))
      (node (ref "U3") (pin "3") (pinfunction "OUTA_3") (pintype "unspecified"))
    )
    (net (code "50") (name "Net-(U4-A0)") (class "Default")
      (node (ref "R17") (pin "2") (pinfunction "2_2") (pintype "unspecified"))
      (node (ref "U4") (pin "1") (pinfunction "A0_1") (pintype "unspecified"))
    )
    (net (code "51") (name "Net-(U4-A1)") (class "Default")
      (node (ref "R18") (pin "2") (pinfunction "2_2") (pintype "unspecified"))
      (node (ref "U4") (pin "2") (pinfunction "A1_2") (pintype "unspecified"))
    )
    (net (code "52") (name "Net-(U4-A2)") (class "Default")
      (node (ref "R19") (pin "2") (pinfunction "2_2") (pintype "unspecified"))
      (node (ref "U4") (pin "3") (pinfunction "A2_3") (pintype "unspecified"))
    )
    (net (code "53") (name "Net-(U4-LED0)") (class "Default")
      (node (ref "R16") (pin "1") (pinfunction "1_1") (pintype "unspecified"))
      (node (ref "U4") (pin "6") (pinfunction "LED0_6") (pintype "unspecified"))
    )
    (net (code "54") (name "Net-(U4-LED1)") (class "Default")
      (node (ref "R14") (pin "1") (pinfunction "1_1") (pintype "unspecified"))
      (node (ref "U4") (pin "7") (pinfunction "LED1_7") (pintype "unspecified"))
    )
    (net (code "55") (name "Net-(U4-LED2)") (class "Default")
      (node (ref "R12") (pin "1") (pinfunction "1_1") (pintype "unspecified"))
      (node (ref "U4") (pin "8") (pinfunction "LED2_8") (pintype "unspecified"))
    )
    (net (code "56") (name "Net-(U4-LED3)") (class "Default")
      (node (ref "R10") (pin "1") (pinfunction "1_1") (pintype "unspecified"))
      (node (ref "U4") (pin "9") (pinfunction "LED3_9") (pintype "unspecified"))
    )
    (net (code "57") (name "Net-(U4-LED4)") (class "Default")
      (node (ref "R8") (pin "1") (pinfunction "1_1") (pintype "unspecified"))
      (node (ref "U4") (pin "10") (pinfunction "LED4_10") (pintype "unspecified"))
    )
    (net (code "58") (name "Net-(U4-LED5)") (class "Default")
      (node (ref "R6") (pin "1") (pinfunction "1_1") (pintype "unspecified"))
      (node (ref "U4") (pin "11") (pinfunction "LED5_11") (pintype "unspecified"))
    )
    (net (code "59") (name "Net-(U4-LED6)") (class "Default")
      (node (ref "R4") (pin "1") (pinfunction "1_1") (pintype "unspecified"))
      (node (ref "U4") (pin "12") (pinfunction "LED6_12") (pintype "unspecified"))
    )
    (net (code "60") (name "Net-(U4-LED7)") (class "Default")
      (node (ref "R2") (pin "1") (pinfunction "1_1") (pintype "unspecified"))
      (node (ref "U4") (pin "13") (pinfunction "LED7_13") (pintype "unspecified"))
    )
    (net (code "61") (name "Net-(U4-LED8)") (class "Default")
      (node (ref "R1") (pin "1") (pinfunction "1_1") (pintype "unspecified"))
      (node (ref "U4") (pin "15") (pinfunction "LED8_15") (pintype "unspecified"))
    )
    (net (code "62") (name "Net-(U4-LED9)") (class "Default")
      (node (ref "R3") (pin "1") (pinfunction "1_1") (pintype "unspecified"))
      (node (ref "U4") (pin "16") (pinfunction "LED9_16") (pintype "unspecified"))
    )
    (net (code "63") (name "Net-(U4-LED10)") (class "Default")
      (node (ref "R5") (pin "1") (pinfunction "1_1") (pintype "unspecified"))
      (node (ref "U4") (pin "17") (pinfunction "LED10_17") (pintype "unspecified"))
    )
    (net (code "64") (name "Net-(U4-LED11)") (class "Default")
      (node (ref "R7") (pin "1") (pinfunction "1_1") (pintype "unspecified"))
      (node (ref "U4") (pin "18") (pinfunction "LED11_18") (pintype "unspecified"))
    )
    (net (code "65") (name "Net-(U4-LED12)") (class "Default")
      (node (ref "R9") (pin "1") (pinfunction "1_1") (pintype "unspecified"))
      (node (ref "U4") (pin "19") (pinfunction "LED12_19") (pintype "unspecified"))
    )
    (net (code "66") (name "Net-(U4-LED13)") (class "Default")
      (node (ref "R11") (pin "1") (pinfunction "1_1") (pintype "unspecified"))
      (node (ref "U4") (pin "20") (pinfunction "LED13_20") (pintype "unspecified"))
    )
    (net (code "67") (name "Net-(U4-LED14)") (class "Default")
      (node (ref "R13") (pin "1") (pinfunction "1_1") (pintype "unspecified"))
      (node (ref "U4") (pin "21") (pinfunction "LED14_21") (pintype "unspecified"))
    )
    (net (code "68") (name "Net-(U4-LED15)") (class "Default")
      (node (ref "R15") (pin "1") (pinfunction "1_1") (pintype "unspecified"))
      (node (ref "U4") (pin "22") (pinfunction "LED15_22") (pintype "unspecified"))
    )
    (net (code "69") (name "Net-(U6-WP#)") (class "Default")
      (node (ref "J27") (pin "1") (pinfunction "1_1") (pintype "unspecified"))
      (node (ref "U6") (pin "7") (pinfunction "WP#_7") (pintype "unspecified"))
    )
    (net (code "70") (name "RST") (class "Default")
      (node (ref "PCB1") (pin "33") (pinfunction "RST_33") (pintype "unspecified"))
      (node (ref "PCB1") (pin "73") (pinfunction "RST_73") (pintype "unspecified"))
    )
    (net (code "71") (name "SCL") (class "Default")
      (node (ref "PCB1") (pin "29") (pinfunction "SCL_29") (pintype "unspecified"))
      (node (ref "PCB1") (pin "69") (pinfunction "SCL_69") (pintype "unspecified"))
      (node (ref "U4") (pin "27") (pinfunction "SDA_27") (pintype "unspecified"))
      (node (ref "U6") (pin "6") (pinfunction "SCL_6") (pintype "unspecified"))
    )
    (net (code "72") (name "SDA") (class "Default")
      (node (ref "PCB1") (pin "39") (pinfunction "SDA_39") (pintype "unspecified"))
      (node (ref "PCB1") (pin "79") (pinfunction "SDA_79") (pintype "unspecified"))
      (node (ref "U4") (pin "26") (pinfunction "SCL_26") (pintype "unspecified"))
      (node (ref "U6") (pin "5") (pinfunction "SDA_5") (pintype "unspecified"))
    )
    (net (code "73") (name "TRACK-1-1") (class "Default")
      (node (ref "PCB1") (pin "10") (pinfunction "BI-1_10") (pintype "unspecified"))
      (node (ref "PCB1") (pin "50") (pinfunction "BO-1_50") (pintype "unspecified"))
    )
    (net (code "74") (name "TRACK-1-2") (class "Default")
      (node (ref "PCB1") (pin "11") (pinfunction "BI-2_11") (pintype "unspecified"))
      (node (ref "PCB1") (pin "51") (pinfunction "BO-2_51") (pintype "unspecified"))
    )
    (net (code "75") (name "TRACK-2-1") (class "Default")
      (node (ref "PCB1") (pin "12") (pinfunction "BI-3_12") (pintype "unspecified"))
      (node (ref "PCB1") (pin "52") (pinfunction "BO-3_52") (pintype "unspecified"))
    )
    (net (code "76") (name "TRACK-2-2") (class "Default")
      (node (ref "PCB1") (pin "13") (pinfunction "BI-4_13") (pintype "unspecified"))
      (node (ref "PCB1") (pin "53") (pinfunction "BO-4_53") (pintype "unspecified"))
    )
    (net (code "77") (name "TRACK-3-1") (class "Default")
      (node (ref "PCB1") (pin "14") (pinfunction "BI-5_14") (pintype "unspecified"))
      (node (ref "PCB1") (pin "54") (pinfunction "BO-5_54") (pintype "unspecified"))
    )
    (net (code "78") (name "TRACK-3-2") (class "Default")
      (node (ref "PCB1") (pin "15") (pinfunction "BI-6_15") (pintype "unspecified"))
      (node (ref "PCB1") (pin "55") (pinfunction "BO-6_55") (pintype "unspecified"))
    )
    (net (code "79") (name "TRACK-4-1") (class "Default")
      (node (ref "PCB1") (pin "16") (pinfunction "BI-7_16") (pintype "unspecified"))
      (node (ref "PCB1") (pin "56") (pinfunction "BO-7_56") (pintype "unspecified"))
    )
    (net (code "80") (name "TRACK-4-2") (class "Default")
      (node (ref "PCB1") (pin "17") (pinfunction "BI-8_17") (pintype "unspecified"))
      (node (ref "PCB1") (pin "57") (pinfunction "BO-8_57") (pintype "unspecified"))
    )
    (net (code "81") (name "VCC") (class "Default")
      (node (ref "C1") (pin "1") (pinfunction "1_1") (pintype "unspecified"))
      (node (ref "C2") (pin "2") (pinfunction "2_2") (pintype "unspecified"))
      (node (ref "C4") (pin "2") (pinfunction "2_2") (pintype "unspecified"))
      (node (ref "C5") (pin "1") (pinfunction "1_1") (pintype "unspecified"))
      (node (ref "J10") (pin "1") (pinfunction "1_1") (pintype "input"))
      (node (ref "J13") (pin "1") (pinfunction "1_1") (pintype "input"))
      (node (ref "J14") (pin "1") (pinfunction "1_1") (pintype "input"))
      (node (ref "J15") (pin "1") (pinfunction "1_1") (pintype "input"))
      (node (ref "J16") (pin "1") (pinfunction "1_1") (pintype "input"))
      (node (ref "J17") (pin "1") (pinfunction "1_1") (pintype "input"))
      (node (ref "J18") (pin "1") (pinfunction "1_1") (pintype "input"))
      (node (ref "J19") (pin "1") (pinfunction "1_1") (pintype "input"))
      (node (ref "J20") (pin "1") (pinfunction "1_1") (pintype "input"))
      (node (ref "J21") (pin "1") (pinfunction "1_1") (pintype "input"))
      (node (ref "J22") (pin "1") (pinfunction "1_1") (pintype "input"))
      (node (ref "J23") (pin "1") (pinfunction "1_1") (pintype "input"))
      (node (ref "J24") (pin "1") (pinfunction "1_1") (pintype "input"))
      (node (ref "J25") (pin "1") (pinfunction "1_1") (pintype "input"))
      (node (ref "J26") (pin "1") (pinfunction "1_1") (pintype "input"))
      (node (ref "J27") (pin "2") (pinfunction "2_2") (pintype "unspecified"))
      (node (ref "J9") (pin "1") (pinfunction "1_1") (pintype "input"))
      (node (ref "PCB1") (pin "28") (pinfunction "VCC_28") (pintype "unspecified"))
      (node (ref "PCB1") (pin "38") (pinfunction "VCC_38") (pintype "unspecified"))
      (node (ref "PCB1") (pin "68") (pinfunction "VCC_68") (pintype "unspecified"))
      (node (ref "PCB1") (pin "78") (pinfunction "VCC_78") (pintype "unspecified"))
      (node (ref "R17") (pin "1") (pinfunction "1_1") (pintype "unspecified"))
      (node (ref "R18") (pin "1") (pinfunction "1_1") (pintype "unspecified"))
      (node (ref "R19") (pin "1") (pinfunction "1_1") (pintype "unspecified"))
      (node (ref "R22") (pin "1") (pinfunction "1_1") (pintype "unspecified"))
      (node (ref "R23") (pin "1") (pinfunction "1_1") (pintype "unspecified"))
      (node (ref "U3") (pin "14") (pinfunction "VDD_14") (pintype "unspecified"))
      (node (ref "U4") (pin "28") (pinfunction "VDD_28") (pintype "unspecified"))
      (node (ref "U6") (pin "8") (pinfunction "VCC_8") (pintype "unspecified"))
    )
    (net (code "82") (name "VS") (class "Default")
      (node (ref "PCB1") (pin "41") (pinfunction "PI-2_41") (pintype "unspecified"))
      (node (ref "PCB1") (pin "81") (pinfunction "PO-2_81") (pintype "unspecified"))
    )
    (net (code "83") (name "unconnected-(J1-Pad2)") (class "Default")
      (node (ref "J1") (pin "2") (pinfunction "2_2") (pintype "unspecified"))
    )
    (net (code "84") (name "unconnected-(J1-Pad4)") (class "Default")
      (node (ref "J1") (pin "4") (pinfunction "4_4") (pintype "unspecified"))
    )
    (net (code "85") (name "unconnected-(J1-Pad6)") (class "Default")
      (node (ref "J1") (pin "6") (pinfunction "6_6") (pintype "unspecified"))
    )
    (net (code "86") (name "unconnected-(J1-Pad8)") (class "Default")
      (node (ref "J1") (pin "8") (pinfunction "8_8") (pintype "unspecified"))
    )
    (net (code "87") (name "unconnected-(J2-Pad2)") (class "Default")
      (node (ref "J2") (pin "2") (pinfunction "2_2") (pintype "unspecified"))
    )
    (net (code "88") (name "unconnected-(J2-Pad4)") (class "Default")
      (node (ref "J2") (pin "4") (pinfunction "4_4") (pintype "unspecified"))
    )
    (net (code "89") (name "unconnected-(J2-Pad6)") (class "Default")
      (node (ref "J2") (pin "6") (pinfunction "6_6") (pintype "unspecified"))
    )
    (net (code "90") (name "unconnected-(J2-Pad8)") (class "Default")
      (node (ref "J2") (pin "8") (pinfunction "8_8") (pintype "unspecified"))
    )
    (net (code "91") (name "unconnected-(J3-Pad2)") (class "Default")
      (node (ref "J3") (pin "2") (pinfunction "2_2") (pintype "unspecified"))
    )
    (net (code "92") (name "unconnected-(J3-Pad4)") (class "Default")
      (node (ref "J3") (pin "4") (pinfunction "4_4") (pintype "unspecified"))
    )
    (net (code "93") (name "unconnected-(J3-Pad6)") (class "Default")
      (node (ref "J3") (pin "6") (pinfunction "6_6") (pintype "unspecified"))
    )
    (net (code "94") (name "unconnected-(J3-Pad8)") (class "Default")
      (node (ref "J3") (pin "8") (pinfunction "8_8") (pintype "unspecified"))
    )
    (net (code "95") (name "unconnected-(J4-Pad2)") (class "Default")
      (node (ref "J4") (pin "2") (pinfunction "2_2") (pintype "unspecified"))
    )
    (net (code "96") (name "unconnected-(J4-Pad4)") (class "Default")
      (node (ref "J4") (pin "4") (pinfunction "4_4") (pintype "unspecified"))
    )
    (net (code "97") (name "unconnected-(J4-Pad6)") (class "Default")
      (node (ref "J4") (pin "6") (pinfunction "6_6") (pintype "unspecified"))
    )
    (net (code "98") (name "unconnected-(J4-Pad8)") (class "Default")
      (node (ref "J4") (pin "8") (pinfunction "8_8") (pintype "unspecified"))
    )
    (net (code "99") (name "unconnected-(J5-Pad2)") (class "Default")
      (node (ref "J5") (pin "2") (pinfunction "2_2") (pintype "unspecified"))
    )
    (net (code "100") (name "unconnected-(J5-Pad4)") (class "Default")
      (node (ref "J5") (pin "4") (pinfunction "4_4") (pintype "unspecified"))
    )
    (net (code "101") (name "unconnected-(J5-Pad6)") (class "Default")
      (node (ref "J5") (pin "6") (pinfunction "6_6") (pintype "unspecified"))
    )
    (net (code "102") (name "unconnected-(J5-Pad8)") (class "Default")
      (node (ref "J5") (pin "8") (pinfunction "8_8") (pintype "unspecified"))
    )
    (net (code "103") (name "unconnected-(J6-Pad2)") (class "Default")
      (node (ref "J6") (pin "2") (pinfunction "2_2") (pintype "unspecified"))
    )
    (net (code "104") (name "unconnected-(J6-Pad4)") (class "Default")
      (node (ref "J6") (pin "4") (pinfunction "4_4") (pintype "unspecified"))
    )
    (net (code "105") (name "unconnected-(J6-Pad6)") (class "Default")
      (node (ref "J6") (pin "6") (pinfunction "6_6") (pintype "unspecified"))
    )
    (net (code "106") (name "unconnected-(J6-Pad8)") (class "Default")
      (node (ref "J6") (pin "8") (pinfunction "8_8") (pintype "unspecified"))
    )
    (net (code "107") (name "unconnected-(J7-Pad2)") (class "Default")
      (node (ref "J7") (pin "2") (pinfunction "2_2") (pintype "unspecified"))
    )
    (net (code "108") (name "unconnected-(J7-Pad4)") (class "Default")
      (node (ref "J7") (pin "4") (pinfunction "4_4") (pintype "unspecified"))
    )
    (net (code "109") (name "unconnected-(J7-Pad6)") (class "Default")
      (node (ref "J7") (pin "6") (pinfunction "6_6") (pintype "unspecified"))
    )
    (net (code "110") (name "unconnected-(J7-Pad8)") (class "Default")
      (node (ref "J7") (pin "8") (pinfunction "8_8") (pintype "unspecified"))
    )
    (net (code "111") (name "unconnected-(J8-Pad2)") (class "Default")
      (node (ref "J8") (pin "2") (pinfunction "2_2") (pintype "unspecified"))
    )
    (net (code "112") (name "unconnected-(J8-Pad4)") (class "Default")
      (node (ref "J8") (pin "4") (pinfunction "4_4") (pintype "unspecified"))
    )
    (net (code "113") (name "unconnected-(J8-Pad6)") (class "Default")
      (node (ref "J8") (pin "6") (pinfunction "6_6") (pintype "unspecified"))
    )
    (net (code "114") (name "unconnected-(J8-Pad8)") (class "Default")
      (node (ref "J8") (pin "8") (pinfunction "8_8") (pintype "unspecified"))
    )
    (net (code "115") (name "unconnected-(J11-Pad1)") (class "Default")
      (node (ref "J11") (pin "1") (pinfunction "1_1") (pintype "unspecified"))
    )
    (net (code "116") (name "unconnected-(J11-Pad2)") (class "Default")
      (node (ref "J11") (pin "2") (pinfunction "2_2") (pintype "unspecified"))
    )
    (net (code "117") (name "unconnected-(J11-Pad3)") (class "Default")
      (node (ref "J11") (pin "3") (pinfunction "3_3") (pintype "unspecified"))
    )
    (net (code "118") (name "unconnected-(J11-Pad4)") (class "Default")
      (node (ref "J11") (pin "4") (pinfunction "4_4") (pintype "unspecified"))
    )
    (net (code "119") (name "unconnected-(J11-Pad5)") (class "Default")
      (node (ref "J11") (pin "5") (pinfunction "5_5") (pintype "unspecified"))
    )
    (net (code "120") (name "unconnected-(J11-Pad6)") (class "Default")
      (node (ref "J11") (pin "6") (pinfunction "6_6") (pintype "unspecified"))
    )
    (net (code "121") (name "unconnected-(J11-Pad7)") (class "Default")
      (node (ref "J11") (pin "7") (pinfunction "7_7") (pintype "unspecified"))
    )
    (net (code "122") (name "unconnected-(J11-Pad8)") (class "Default")
      (node (ref "J11") (pin "8") (pinfunction "8_8") (pintype "unspecified"))
    )
    (net (code "123") (name "unconnected-(J12-Pad1)") (class "Default")
      (node (ref "J12") (pin "1") (pinfunction "1_1") (pintype "unspecified"))
    )
    (net (code "124") (name "unconnected-(J12-Pad2)") (class "Default")
      (node (ref "J12") (pin "2") (pinfunction "2_2") (pintype "unspecified"))
    )
    (net (code "125") (name "unconnected-(J12-Pad3)") (class "Default")
      (node (ref "J12") (pin "3") (pinfunction "3_3") (pintype "unspecified"))
    )
    (net (code "126") (name "unconnected-(J12-Pad4)") (class "Default")
      (node (ref "J12") (pin "4") (pinfunction "4_4") (pintype "unspecified"))
    )
    (net (code "127") (name "unconnected-(J12-Pad5)") (class "Default")
      (node (ref "J12") (pin "5") (pinfunction "5_5") (pintype "unspecified"))
    )
    (net (code "128") (name "unconnected-(J12-Pad6)") (class "Default")
      (node (ref "J12") (pin "6") (pinfunction "6_6") (pintype "unspecified"))
    )
    (net (code "129") (name "unconnected-(J12-Pad7)") (class "Default")
      (node (ref "J12") (pin "7") (pinfunction "7_7") (pintype "unspecified"))
    )
    (net (code "130") (name "unconnected-(J12-Pad8)") (class "Default")
      (node (ref "J12") (pin "8") (pinfunction "8_8") (pintype "unspecified"))
    )
    (net (code "131") (name "unconnected-(K1-Pad1)") (class "Default")
      (node (ref "K1") (pin "1") (pinfunction "1_1") (pintype "unspecified"))
    )
    (net (code "132") (name "unconnected-(K1-Pad3)") (class "Default")
      (node (ref "K1") (pin "3") (pinfunction "3_3") (pintype "unspecified"))
    )
    (net (code "133") (name "unconnected-(K1-Pad6)") (class "Default")
      (node (ref "K1") (pin "6") (pinfunction "6_6") (pintype "unspecified"))
    )
    (net (code "134") (name "unconnected-(K1-Pad8)") (class "Default")
      (node (ref "K1") (pin "8") (pinfunction "8_8") (pintype "unspecified"))
    )
    (net (code "135") (name "unconnected-(K2-Pad1)") (class "Default")
      (node (ref "K2") (pin "1") (pinfunction "1_1") (pintype "unspecified"))
    )
    (net (code "136") (name "unconnected-(K2-Pad3)") (class "Default")
      (node (ref "K2") (pin "3") (pinfunction "3_3") (pintype "unspecified"))
    )
    (net (code "137") (name "unconnected-(K2-Pad6)") (class "Default")
      (node (ref "K2") (pin "6") (pinfunction "6_6") (pintype "unspecified"))
    )
    (net (code "138") (name "unconnected-(K2-Pad8)") (class "Default")
      (node (ref "K2") (pin "8") (pinfunction "8_8") (pintype "unspecified"))
    )
    (net (code "139") (name "unconnected-(K3-Pad1)") (class "Default")
      (node (ref "K3") (pin "1") (pinfunction "1_1") (pintype "unspecified"))
    )
    (net (code "140") (name "unconnected-(K3-Pad3)") (class "Default")
      (node (ref "K3") (pin "3") (pinfunction "3_3") (pintype "unspecified"))
    )
    (net (code "141") (name "unconnected-(K3-Pad6)") (class "Default")
      (node (ref "K3") (pin "6") (pinfunction "6_6") (pintype "unspecified"))
    )
    (net (code "142") (name "unconnected-(K3-Pad8)") (class "Default")
      (node (ref "K3") (pin "8") (pinfunction "8_8") (pintype "unspecified"))
    )
    (net (code "143") (name "unconnected-(K4-Pad1)") (class "Default")
      (node (ref "K4") (pin "1") (pinfunction "1_1") (pintype "unspecified"))
    )
    (net (code "144") (name "unconnected-(K4-Pad3)") (class "Default")
      (node (ref "K4") (pin "3") (pinfunction "3_3") (pintype "unspecified"))
    )
    (net (code "145") (name "unconnected-(K4-Pad6)") (class "Default")
      (node (ref "K4") (pin "6") (pinfunction "6_6") (pintype "unspecified"))
    )
    (net (code "146") (name "unconnected-(K4-Pad8)") (class "Default")
      (node (ref "K4") (pin "8") (pinfunction "8_8") (pintype "unspecified"))
    )
    (net (code "147") (name "unconnected-(K5-Pad1)") (class "Default")
      (node (ref "K5") (pin "1") (pinfunction "1_1") (pintype "unspecified"))
    )
    (net (code "148") (name "unconnected-(K5-Pad3)") (class "Default")
      (node (ref "K5") (pin "3") (pinfunction "3_3") (pintype "unspecified"))
    )
    (net (code "149") (name "unconnected-(K5-Pad6)") (class "Default")
      (node (ref "K5") (pin "6") (pinfunction "6_6") (pintype "unspecified"))
    )
    (net (code "150") (name "unconnected-(K5-Pad8)") (class "Default")
      (node (ref "K5") (pin "8") (pinfunction "8_8") (pintype "unspecified"))
    )
    (net (code "151") (name "unconnected-(K6-Pad1)") (class "Default")
      (node (ref "K6") (pin "1") (pinfunction "1_1") (pintype "unspecified"))
    )
    (net (code "152") (name "unconnected-(K6-Pad3)") (class "Default")
      (node (ref "K6") (pin "3") (pinfunction "3_3") (pintype "unspecified"))
    )
    (net (code "153") (name "unconnected-(K6-Pad6)") (class "Default")
      (node (ref "K6") (pin "6") (pinfunction "6_6") (pintype "unspecified"))
    )
    (net (code "154") (name "unconnected-(K6-Pad8)") (class "Default")
      (node (ref "K6") (pin "8") (pinfunction "8_8") (pintype "unspecified"))
    )
    (net (code "155") (name "unconnected-(K7-Pad1)") (class "Default")
      (node (ref "K7") (pin "1") (pinfunction "1_1") (pintype "unspecified"))
    )
    (net (code "156") (name "unconnected-(K7-Pad3)") (class "Default")
      (node (ref "K7") (pin "3") (pinfunction "3_3") (pintype "unspecified"))
    )
    (net (code "157") (name "unconnected-(K7-Pad6)") (class "Default")
      (node (ref "K7") (pin "6") (pinfunction "6_6") (pintype "unspecified"))
    )
    (net (code "158") (name "unconnected-(K7-Pad8)") (class "Default")
      (node (ref "K7") (pin "8") (pinfunction "8_8") (pintype "unspecified"))
    )
    (net (code "159") (name "unconnected-(K8-Pad1)") (class "Default")
      (node (ref "K8") (pin "1") (pinfunction "1_1") (pintype "unspecified"))
    )
    (net (code "160") (name "unconnected-(K8-Pad3)") (class "Default")
      (node (ref "K8") (pin "3") (pinfunction "3_3") (pintype "unspecified"))
    )
    (net (code "161") (name "unconnected-(K8-Pad6)") (class "Default")
      (node (ref "K8") (pin "6") (pinfunction "6_6") (pintype "unspecified"))
    )
    (net (code "162") (name "unconnected-(K8-Pad8)") (class "Default")
      (node (ref "K8") (pin "8") (pinfunction "8_8") (pintype "unspecified"))
    )
    (net (code "163") (name "unconnected-(K9-Pad1)") (class "Default")
      (node (ref "K9") (pin "1") (pinfunction "1_1") (pintype "unspecified"))
    )
    (net (code "164") (name "unconnected-(K9-Pad3)") (class "Default")
      (node (ref "K9") (pin "3") (pinfunction "3_3") (pintype "unspecified"))
    )
    (net (code "165") (name "unconnected-(K9-Pad6)") (class "Default")
      (node (ref "K9") (pin "6") (pinfunction "6_6") (pintype "unspecified"))
    )
    (net (code "166") (name "unconnected-(K9-Pad8)") (class "Default")
      (node (ref "K9") (pin "8") (pinfunction "8_8") (pintype "unspecified"))
    )
    (net (code "167") (name "unconnected-(K10-Pad1)") (class "Default")
      (node (ref "K10") (pin "1") (pinfunction "1_1") (pintype "unspecified"))
    )
    (net (code "168") (name "unconnected-(K10-Pad3)") (class "Default")
      (node (ref "K10") (pin "3") (pinfunction "3_3") (pintype "unspecified"))
    )
    (net (code "169") (name "unconnected-(K10-Pad6)") (class "Default")
      (node (ref "K10") (pin "6") (pinfunction "6_6") (pintype "unspecified"))
    )
    (net (code "170") (name "unconnected-(K10-Pad8)") (class "Default")
      (node (ref "K10") (pin "8") (pinfunction "8_8") (pintype "unspecified"))
    )
    (net (code "171") (name "unconnected-(K11-Pad1)") (class "Default")
      (node (ref "K11") (pin "1") (pinfunction "1_1") (pintype "unspecified"))
    )
    (net (code "172") (name "unconnected-(K11-Pad3)") (class "Default")
      (node (ref "K11") (pin "3") (pinfunction "3_3") (pintype "unspecified"))
    )
    (net (code "173") (name "unconnected-(K11-Pad6)") (class "Default")
      (node (ref "K11") (pin "6") (pinfunction "6_6") (pintype "unspecified"))
    )
    (net (code "174") (name "unconnected-(K11-Pad8)") (class "Default")
      (node (ref "K11") (pin "8") (pinfunction "8_8") (pintype "unspecified"))
    )
    (net (code "175") (name "unconnected-(K12-Pad1)") (class "Default")
      (node (ref "K12") (pin "1") (pinfunction "1_1") (pintype "unspecified"))
    )
    (net (code "176") (name "unconnected-(K12-Pad3)") (class "Default")
      (node (ref "K12") (pin "3") (pinfunction "3_3") (pintype "unspecified"))
    )
    (net (code "177") (name "unconnected-(K12-Pad6)") (class "Default")
      (node (ref "K12") (pin "6") (pinfunction "6_6") (pintype "unspecified"))
    )
    (net (code "178") (name "unconnected-(K12-Pad8)") (class "Default")
      (node (ref "K12") (pin "8") (pinfunction "8_8") (pintype "unspecified"))
    )
    (net (code "179") (name "unconnected-(K13-Pad1)") (class "Default")
      (node (ref "K13") (pin "1") (pinfunction "1_1") (pintype "unspecified"))
    )
    (net (code "180") (name "unconnected-(K13-Pad3)") (class "Default")
      (node (ref "K13") (pin "3") (pinfunction "3_3") (pintype "unspecified"))
    )
    (net (code "181") (name "unconnected-(K13-Pad6)") (class "Default")
      (node (ref "K13") (pin "6") (pinfunction "6_6") (pintype "unspecified"))
    )
    (net (code "182") (name "unconnected-(K13-Pad8)") (class "Default")
      (node (ref "K13") (pin "8") (pinfunction "8_8") (pintype "unspecified"))
    )
    (net (code "183") (name "unconnected-(K14-Pad1)") (class "Default")
      (node (ref "K14") (pin "1") (pinfunction "1_1") (pintype "unspecified"))
    )
    (net (code "184") (name "unconnected-(K14-Pad3)") (class "Default")
      (node (ref "K14") (pin "3") (pinfunction "3_3") (pintype "unspecified"))
    )
    (net (code "185") (name "unconnected-(K14-Pad6)") (class "Default")
      (node (ref "K14") (pin "6") (pinfunction "6_6") (pintype "unspecified"))
    )
    (net (code "186") (name "unconnected-(K14-Pad8)") (class "Default")
      (node (ref "K14") (pin "8") (pinfunction "8_8") (pintype "unspecified"))
    )
    (net (code "187") (name "unconnected-(K15-Pad1)") (class "Default")
      (node (ref "K15") (pin "1") (pinfunction "1_1") (pintype "unspecified"))
    )
    (net (code "188") (name "unconnected-(K15-Pad3)") (class "Default")
      (node (ref "K15") (pin "3") (pinfunction "3_3") (pintype "unspecified"))
    )
    (net (code "189") (name "unconnected-(K15-Pad6)") (class "Default")
      (node (ref "K15") (pin "6") (pinfunction "6_6") (pintype "unspecified"))
    )
    (net (code "190") (name "unconnected-(K15-Pad8)") (class "Default")
      (node (ref "K15") (pin "8") (pinfunction "8_8") (pintype "unspecified"))
    )
    (net (code "191") (name "unconnected-(K16-Pad1)") (class "Default")
      (node (ref "K16") (pin "1") (pinfunction "1_1") (pintype "unspecified"))
    )
    (net (code "192") (name "unconnected-(K16-Pad3)") (class "Default")
      (node (ref "K16") (pin "3") (pinfunction "3_3") (pintype "unspecified"))
    )
    (net (code "193") (name "unconnected-(K16-Pad6)") (class "Default")
      (node (ref "K16") (pin "6") (pinfunction "6_6") (pintype "unspecified"))
    )
    (net (code "194") (name "unconnected-(K16-Pad8)") (class "Default")
      (node (ref "K16") (pin "8") (pinfunction "8_8") (pintype "unspecified"))
    )
    (net (code "195") (name "unconnected-(PCB1-DCC-1-Pad20)") (class "Default")
      (node (ref "PCB1") (pin "20") (pinfunction "DCC-1_20") (pintype "unspecified+no_connect"))
    )
    (net (code "196") (name "unconnected-(PCB1-DCC-1-Pad60)") (class "Default")
      (node (ref "PCB1") (pin "60") (pinfunction "DCC-1_60") (pintype "unspecified+no_connect"))
    )
    (net (code "197") (name "unconnected-(PCB1-DCC-2-Pad30)") (class "Default")
      (node (ref "PCB1") (pin "30") (pinfunction "DCC-2_30") (pintype "unspecified+no_connect"))
    )
    (net (code "198") (name "unconnected-(PCB1-DCC-2-Pad70)") (class "Default")
      (node (ref "PCB1") (pin "70") (pinfunction "DCC-2_70") (pintype "unspecified+no_connect"))
    )
    (net (code "199") (name "unconnected-(PCB1-DIO-0-Pad24)") (class "Default")
      (node (ref "PCB1") (pin "24") (pinfunction "DIO-0_24") (pintype "unspecified+no_connect"))
    )
    (net (code "200") (name "unconnected-(PCB1-DIO-0-Pad64)") (class "Default")
      (node (ref "PCB1") (pin "64") (pinfunction "DIO-0_64") (pintype "unspecified+no_connect"))
    )
    (net (code "201") (name "unconnected-(PCB1-DIO-1-Pad34)") (class "Default")
      (node (ref "PCB1") (pin "34") (pinfunction "DIO-1_34") (pintype "unspecified+no_connect"))
    )
    (net (code "202") (name "unconnected-(PCB1-DIO-1-Pad74)") (class "Default")
      (node (ref "PCB1") (pin "74") (pinfunction "DIO-1_74") (pintype "unspecified+no_connect"))
    )
    (net (code "203") (name "unconnected-(PCB1-DIO-2-Pad25)") (class "Default")
      (node (ref "PCB1") (pin "25") (pinfunction "DIO-2_25") (pintype "unspecified+no_connect"))
    )
    (net (code "204") (name "unconnected-(PCB1-DIO-2-Pad65)") (class "Default")
      (node (ref "PCB1") (pin "65") (pinfunction "DIO-2_65") (pintype "unspecified+no_connect"))
    )
    (net (code "205") (name "unconnected-(PCB1-DIO-3-Pad35)") (class "Default")
      (node (ref "PCB1") (pin "35") (pinfunction "DIO-3_35") (pintype "unspecified+no_connect"))
    )
    (net (code "206") (name "unconnected-(PCB1-DIO-3-Pad75)") (class "Default")
      (node (ref "PCB1") (pin "75") (pinfunction "DIO-3_75") (pintype "unspecified+no_connect"))
    )
    (net (code "207") (name "unconnected-(PCB1-DIO-4-Pad26)") (class "Default")
      (node (ref "PCB1") (pin "26") (pinfunction "DIO-4_26") (pintype "unspecified+no_connect"))
    )
    (net (code "208") (name "unconnected-(PCB1-DIO-4-Pad66)") (class "Default")
      (node (ref "PCB1") (pin "66") (pinfunction "DIO-4_66") (pintype "unspecified+no_connect"))
    )
    (net (code "209") (name "unconnected-(PCB1-DIO-5-Pad36)") (class "Default")
      (node (ref "PCB1") (pin "36") (pinfunction "DIO-5_36") (pintype "unspecified+no_connect"))
    )
    (net (code "210") (name "unconnected-(PCB1-DIO-5-Pad76)") (class "Default")
      (node (ref "PCB1") (pin "76") (pinfunction "DIO-5_76") (pintype "unspecified+no_connect"))
    )
    (net (code "211") (name "unconnected-(PCB1-DIO-6-Pad27)") (class "Default")
      (node (ref "PCB1") (pin "27") (pinfunction "DIO-6_27") (pintype "unspecified+no_connect"))
    )
    (net (code "212") (name "unconnected-(PCB1-DIO-6-Pad67)") (class "Default")
      (node (ref "PCB1") (pin "67") (pinfunction "DIO-6_67") (pintype "unspecified+no_connect"))
    )
    (net (code "213") (name "unconnected-(PCB1-DIO-7-Pad37)") (class "Default")
      (node (ref "PCB1") (pin "37") (pinfunction "DIO-7_37") (pintype "unspecified+no_connect"))
    )
    (net (code "214") (name "unconnected-(PCB1-DIO-7-Pad77)") (class "Default")
      (node (ref "PCB1") (pin "77") (pinfunction "DIO-7_77") (pintype "unspecified+no_connect"))
    )
    (net (code "215") (name "unconnected-(PCB1-PI-3-Pad42)") (class "Default")
      (node (ref "PCB1") (pin "42") (pinfunction "PI-3_42") (pintype "unspecified+no_connect"))
    )
    (net (code "216") (name "unconnected-(PCB1-PI-4-Pad43)") (class "Default")
      (node (ref "PCB1") (pin "43") (pinfunction "PI-4_43") (pintype "unspecified+no_connect"))
    )
    (net (code "217") (name "unconnected-(PCB1-PI-5-Pad44)") (class "Default")
      (node (ref "PCB1") (pin "44") (pinfunction "PI-5_44") (pintype "unspecified+no_connect"))
    )
    (net (code "218") (name "unconnected-(PCB1-PI-6-Pad45)") (class "Default")
      (node (ref "PCB1") (pin "45") (pinfunction "PI-6_45") (pintype "unspecified+no_connect"))
    )
    (net (code "219") (name "unconnected-(PCB1-PI-7-Pad46)") (class "Default")
      (node (ref "PCB1") (pin "46") (pinfunction "PI-7_46") (pintype "unspecified+no_connect"))
    )
    (net (code "220") (name "unconnected-(PCB1-PI-8-Pad47)") (class "Default")
      (node (ref "PCB1") (pin "47") (pinfunction "PI-8_47") (pintype "unspecified+no_connect"))
    )
    (net (code "221") (name "unconnected-(PCB1-PO-3-Pad82)") (class "Default")
      (node (ref "PCB1") (pin "82") (pinfunction "PO-3_82") (pintype "unspecified+no_connect"))
    )
    (net (code "222") (name "unconnected-(PCB1-PO-4-Pad83)") (class "Default")
      (node (ref "PCB1") (pin "83") (pinfunction "PO-4_83") (pintype "unspecified+no_connect"))
    )
    (net (code "223") (name "unconnected-(PCB1-PO-5-Pad84)") (class "Default")
      (node (ref "PCB1") (pin "84") (pinfunction "PO-5_84") (pintype "unspecified+no_connect"))
    )
    (net (code "224") (name "unconnected-(PCB1-PO-6-Pad85)") (class "Default")
      (node (ref "PCB1") (pin "85") (pinfunction "PO-6_85") (pintype "unspecified+no_connect"))
    )
    (net (code "225") (name "unconnected-(PCB1-PO-7-Pad86)") (class "Default")
      (node (ref "PCB1") (pin "86") (pinfunction "PO-7_86") (pintype "unspecified+no_connect"))
    )
    (net (code "226") (name "unconnected-(PCB1-PO-8-Pad87)") (class "Default")
      (node (ref "PCB1") (pin "87") (pinfunction "PO-8_87") (pintype "unspecified+no_connect"))
    )
    (net (code "227") (name "unconnected-(U1-1C-Pad18)") (class "Default")
      (node (ref "U1") (pin "18") (pinfunction "1C_18") (pintype "unspecified"))
    )
    (net (code "228") (name "unconnected-(U1-2C-Pad17)") (class "Default")
      (node (ref "U1") (pin "17") (pinfunction "2C_17") (pintype "unspecified"))
    )
    (net (code "229") (name "unconnected-(U1-3C-Pad16)") (class "Default")
      (node (ref "U1") (pin "16") (pinfunction "3C_16") (pintype "unspecified"))
    )
    (net (code "230") (name "unconnected-(U1-4C-Pad15)") (class "Default")
      (node (ref "U1") (pin "15") (pinfunction "4C_15") (pintype "unspecified"))
    )
    (net (code "231") (name "unconnected-(U1-5C-Pad14)") (class "Default")
      (node (ref "U1") (pin "14") (pinfunction "5C_14") (pintype "unspecified"))
    )
    (net (code "232") (name "unconnected-(U1-6C-Pad13)") (class "Default")
      (node (ref "U1") (pin "13") (pinfunction "6C_13") (pintype "unspecified"))
    )
    (net (code "233") (name "unconnected-(U1-7C-Pad12)") (class "Default")
      (node (ref "U1") (pin "12") (pinfunction "7C_12") (pintype "unspecified"))
    )
    (net (code "234") (name "unconnected-(U1-8C-Pad11)") (class "Default")
      (node (ref "U1") (pin "11") (pinfunction "8C_11") (pintype "unspecified"))
    )
    (net (code "235") (name "unconnected-(U1-COM-Pad10)") (class "Default")
      (node (ref "U1") (pin "10") (pinfunction "COM_10") (pintype "unspecified"))
    )
    (net (code "236") (name "unconnected-(U1-GND-Pad9)") (class "Default")
      (node (ref "U1") (pin "9") (pinfunction "GND_9") (pintype "unspecified"))
    )
    (net (code "237") (name "unconnected-(U2-1C-Pad18)") (class "Default")
      (node (ref "U2") (pin "18") (pinfunction "1C_18") (pintype "unspecified"))
    )
    (net (code "238") (name "unconnected-(U2-2C-Pad17)") (class "Default")
      (node (ref "U2") (pin "17") (pinfunction "2C_17") (pintype "unspecified"))
    )
    (net (code "239") (name "unconnected-(U2-3C-Pad16)") (class "Default")
      (node (ref "U2") (pin "16") (pinfunction "3C_16") (pintype "unspecified"))
    )
    (net (code "240") (name "unconnected-(U2-4C-Pad15)") (class "Default")
      (node (ref "U2") (pin "15") (pinfunction "4C_15") (pintype "unspecified"))
    )
    (net (code "241") (name "unconnected-(U2-5C-Pad14)") (class "Default")
      (node (ref "U2") (pin "14") (pinfunction "5C_14") (pintype "unspecified"))
    )
    (net (code "242") (name "unconnected-(U2-6C-Pad13)") (class "Default")
      (node (ref "U2") (pin "13") (pinfunction "6C_13") (pintype "unspecified"))
    )
    (net (code "243") (name "unconnected-(U2-7C-Pad12)") (class "Default")
      (node (ref "U2") (pin "12") (pinfunction "7C_12") (pintype "unspecified"))
    )
    (net (code "244") (name "unconnected-(U2-8C-Pad11)") (class "Default")
      (node (ref "U2") (pin "11") (pinfunction "8C_11") (pintype "unspecified"))
    )
    (net (code "245") (name "unconnected-(U2-COM-Pad10)") (class "Default")
      (node (ref "U2") (pin "10") (pinfunction "COM_10") (pintype "unspecified"))
    )
    (net (code "246") (name "unconnected-(U2-GND-Pad9)") (class "Default")
      (node (ref "U2") (pin "9") (pinfunction "GND_9") (pintype "unspecified"))
    )
    (net (code "247") (name "unconnected-(U3-OUTB-Pad4)") (class "Default")
      (node (ref "U3") (pin "4") (pinfunction "OUTB_4") (pintype "unspecified+no_connect"))
    )
    (net (code "248") (name "unconnected-(U4-EXTCLK-Pad25)") (class "Default")
      (node (ref "U4") (pin "25") (pinfunction "EXTCLK_25") (pintype "unspecified+no_connect"))
    )
    (net (code "249") (name "unconnected-(U4-OE#-Pad23)") (class "Default")
      (node (ref "U4") (pin "23") (pinfunction "OE#_23") (pintype "unspecified+no_connect"))
    )
    (net (code "250") (name "unconnected-(U5-A0-Pad21)") (class "Default")
      (node (ref "U5") (pin "21") (pinfunction "A0_21") (pintype "unspecified"))
    )
    (net (code "251") (name "unconnected-(U5-A1-Pad2)") (class "Default")
      (node (ref "U5") (pin "2") (pinfunction "A1_2") (pintype "unspecified"))
    )
    (net (code "252") (name "unconnected-(U5-A2-Pad3)") (class "Default")
      (node (ref "U5") (pin "3") (pinfunction "A2_3") (pintype "unspecified"))
    )
    (net (code "253") (name "unconnected-(U5-INT#-Pad1)") (class "Default")
      (node (ref "U5") (pin "1") (pinfunction "INT#_1") (pintype "unspecified"))
    )
    (net (code "254") (name "unconnected-(U5-SCL-Pad22)") (class "Default")
      (node (ref "U5") (pin "22") (pinfunction "SCL_22") (pintype "unspecified"))
    )
    (net (code "255") (name "unconnected-(U5-SDA-Pad23)") (class "Default")
      (node (ref "U5") (pin "23") (pinfunction "SDA_23") (pintype "unspecified"))
    )
    (net (code "256") (name "unconnected-(U5-VDD-Pad24)") (class "Default")
      (node (ref "U5") (pin "24") (pinfunction "VDD_24") (pintype "unspecified"))
    )
    (net (code "257") (name "unconnected-(U5-VSS-Pad12)") (class "Default")
      (node (ref "U5") (pin "12") (pinfunction "VSS_12") (pintype "unspecified"))
    )
  )
)
